# FatPapa1_ISTA.net
KiCad netlist of a schematic drawn in EAGLE
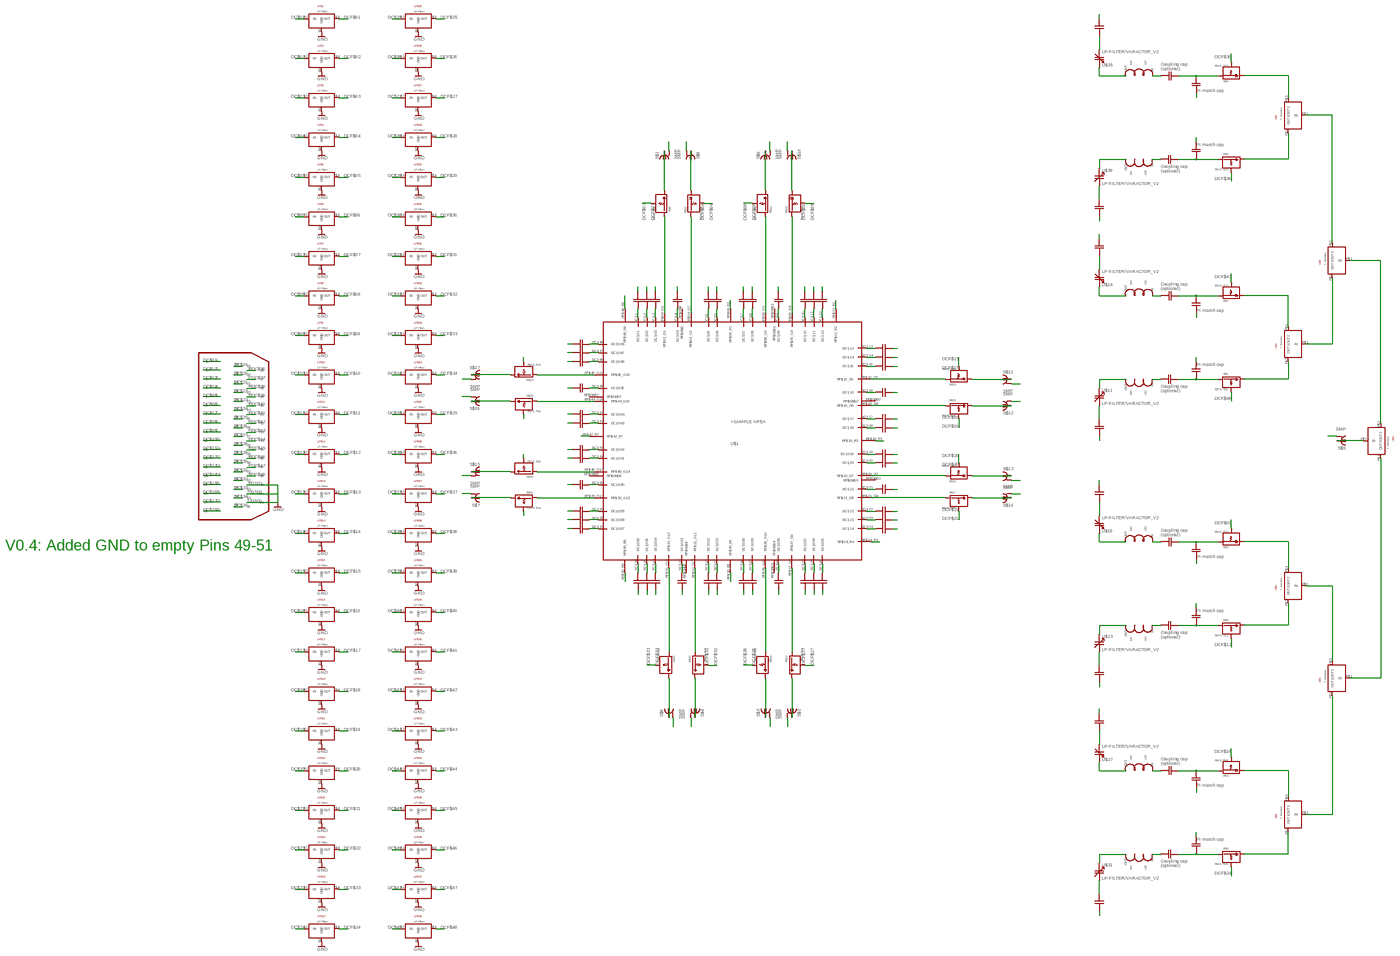
[diagram p0: schematic, sheet 1, overview]
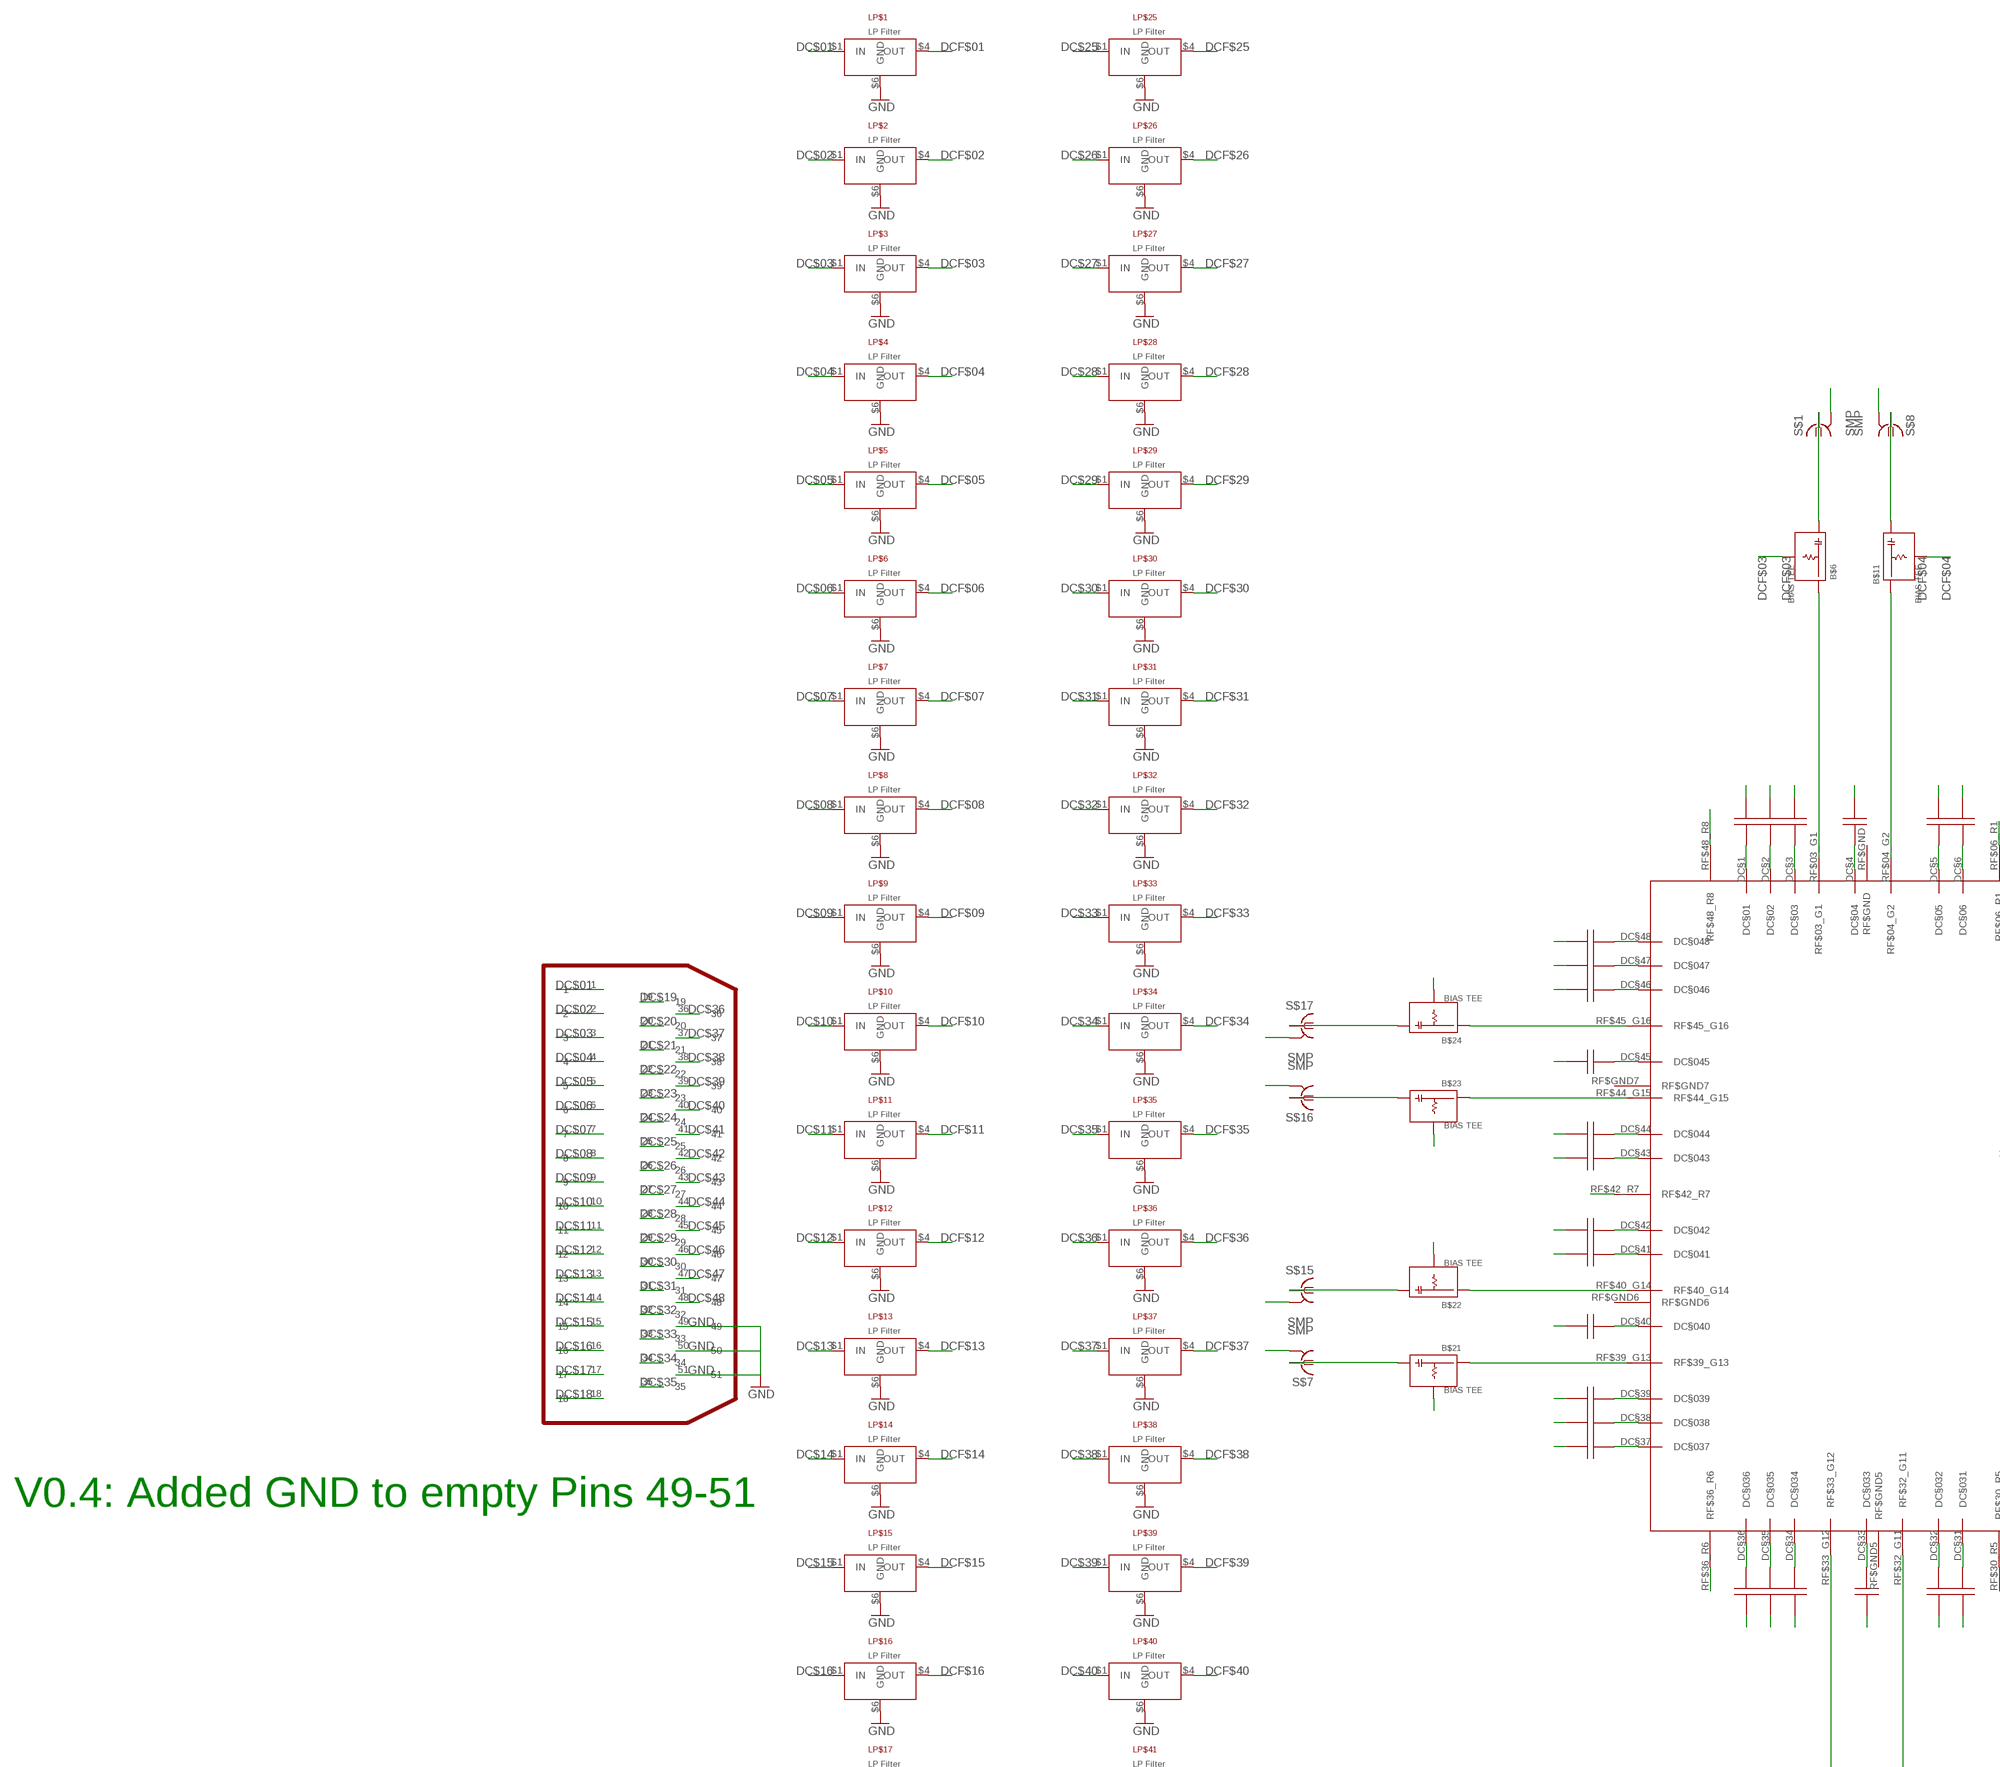
[diagram p1: schematic, sheet 1, part 1 of 4]
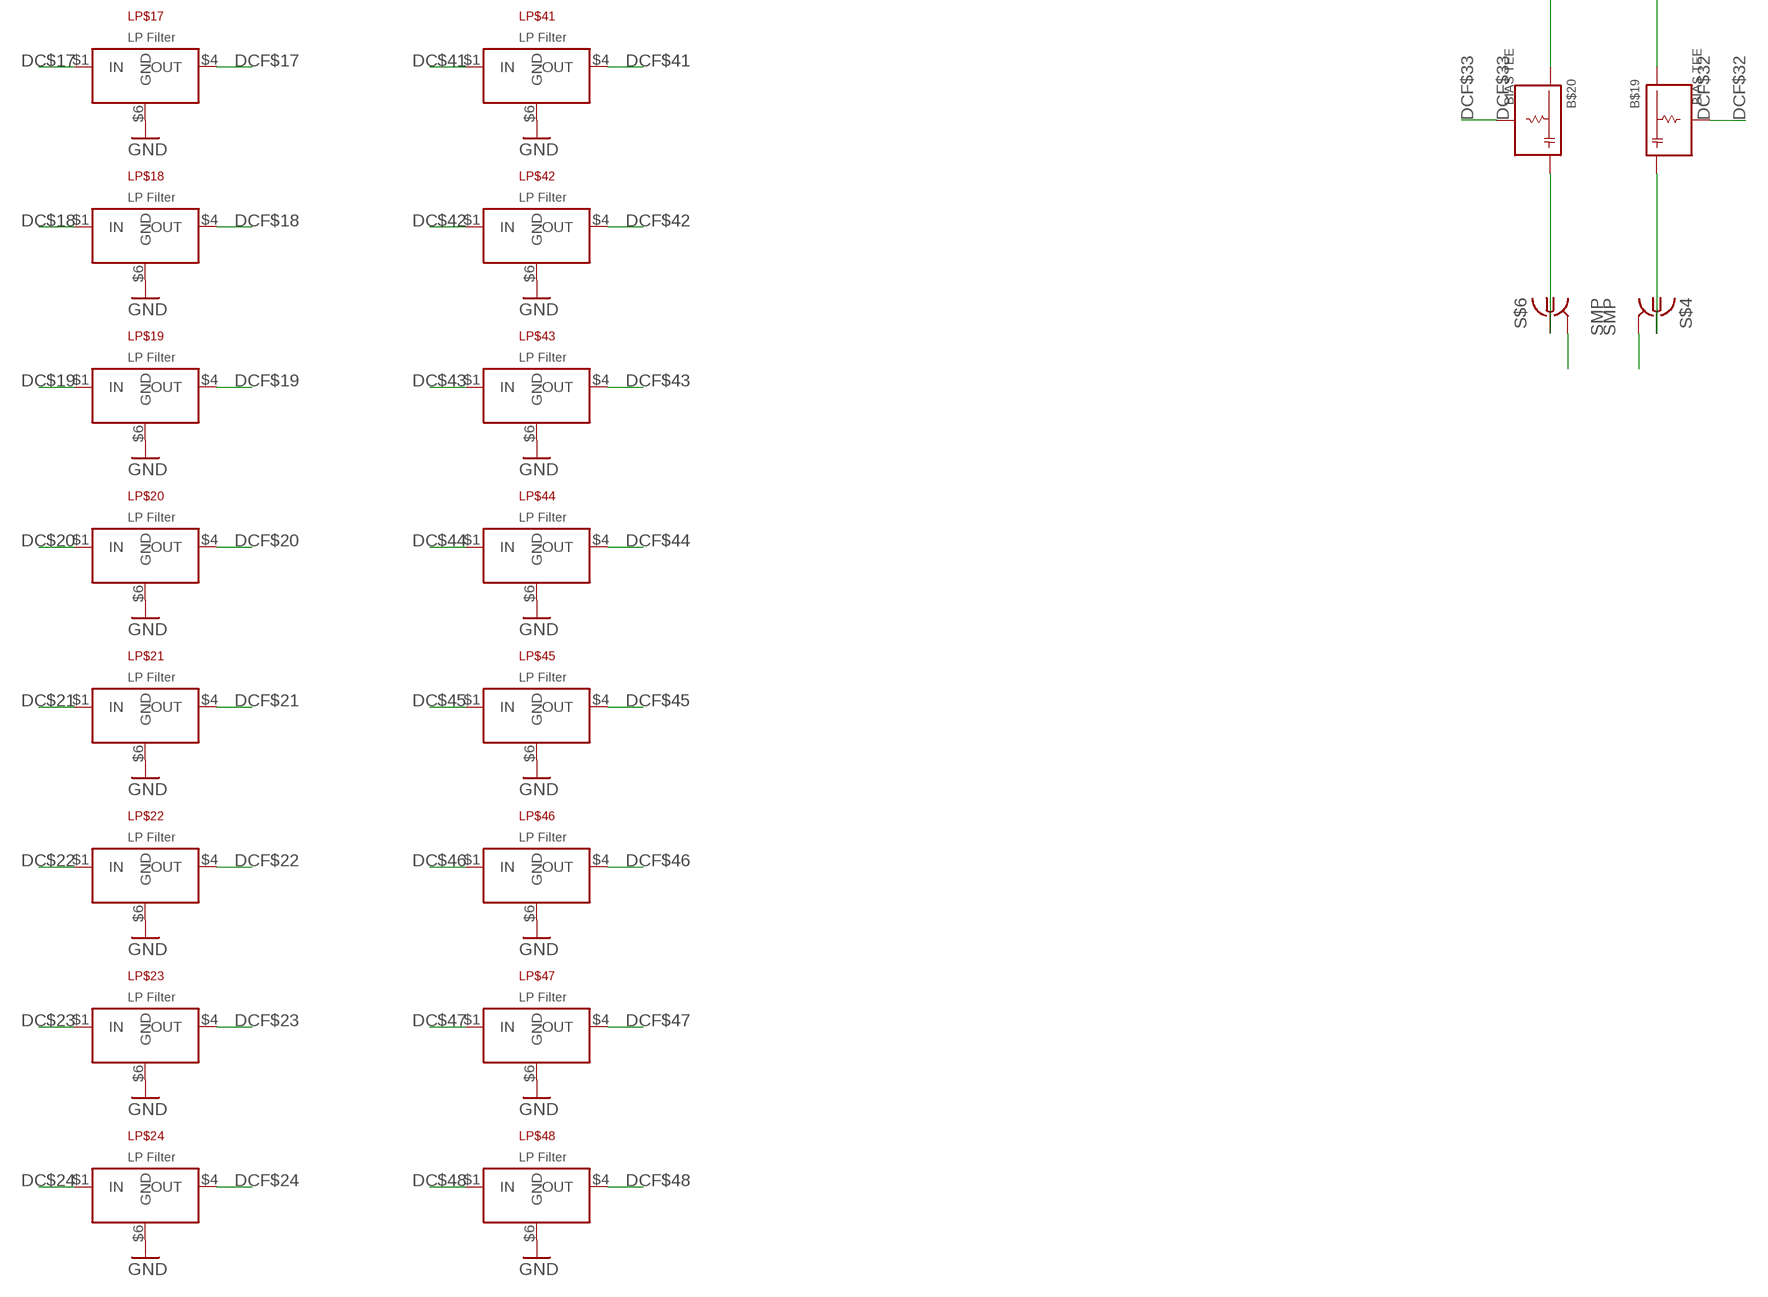
[diagram p2: schematic, sheet 1, part 2 of 4]
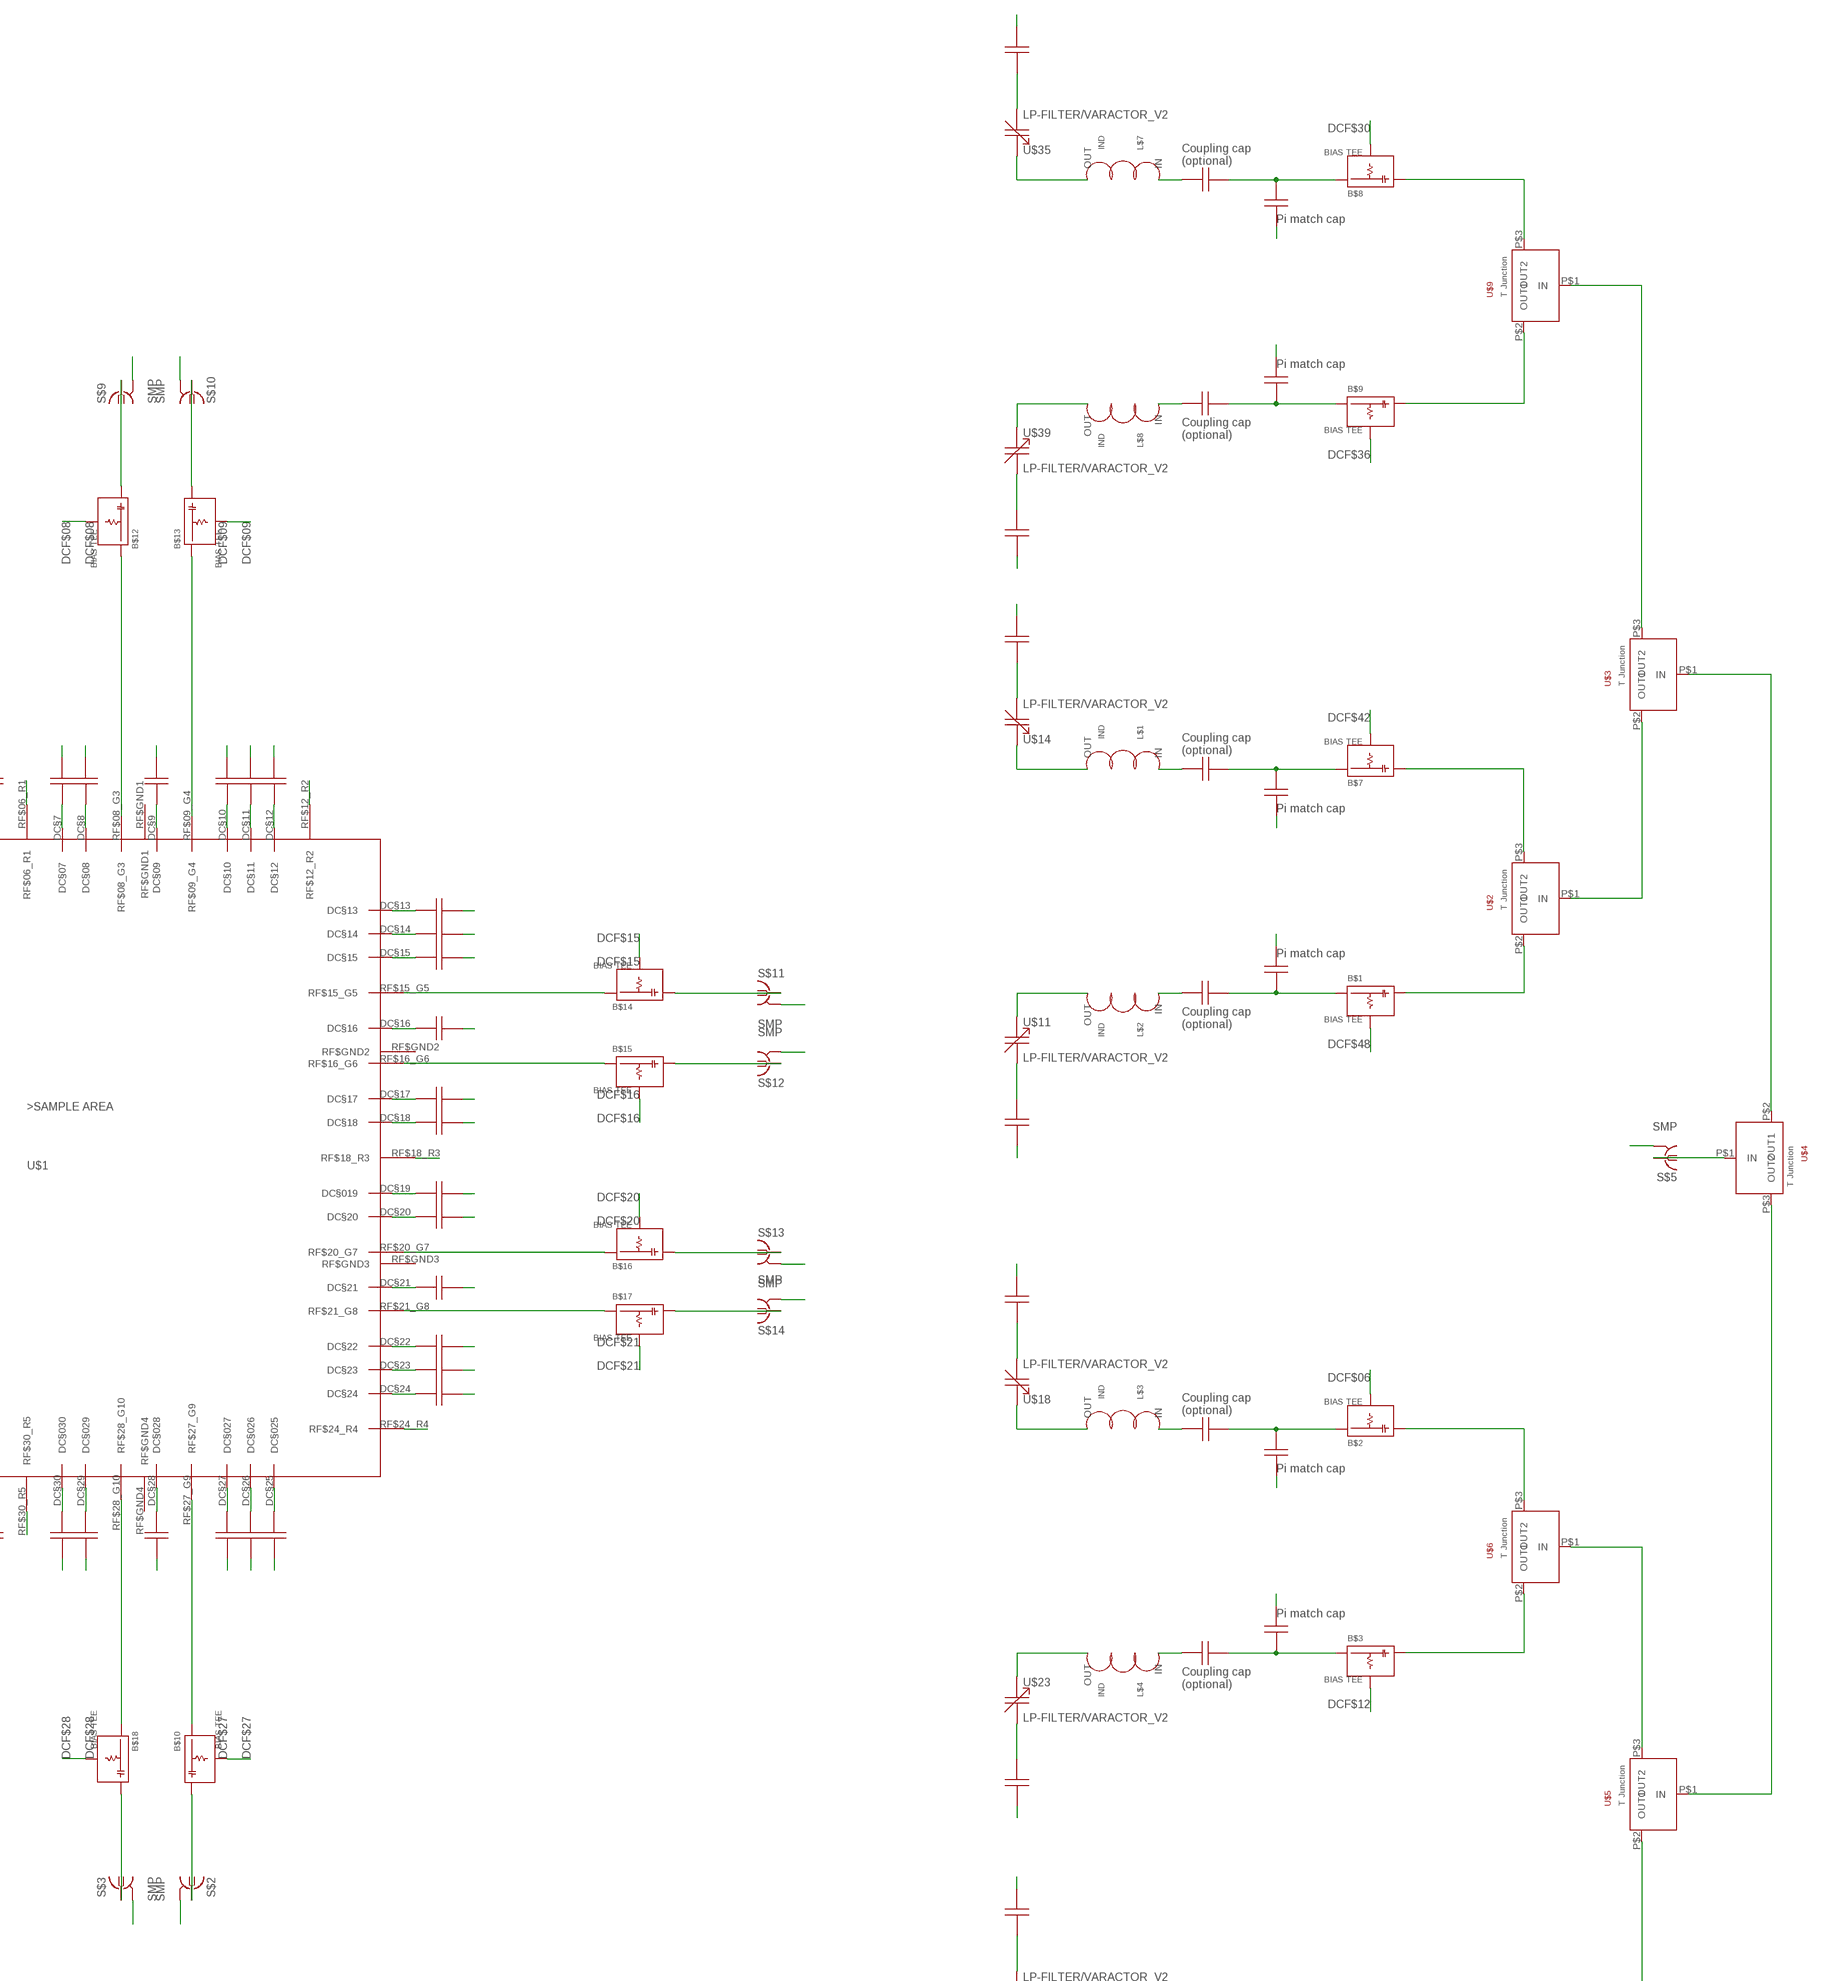
[diagram p3: schematic, sheet 1, part 3 of 4]
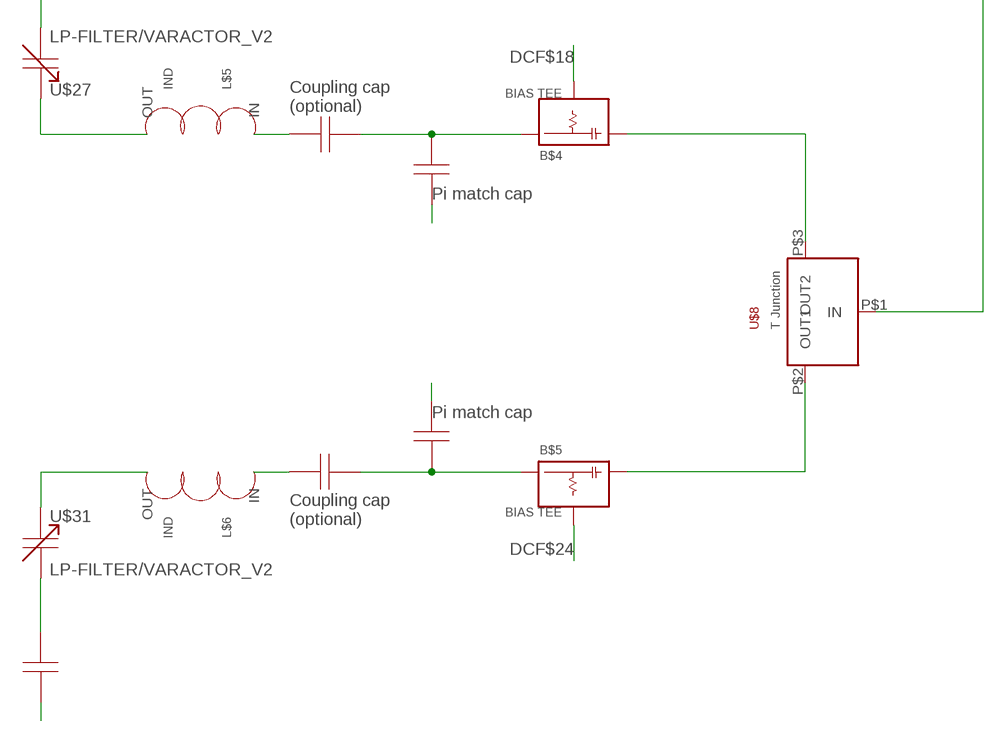
[diagram p4: schematic, sheet 1, part 4 of 4]

(export (version "E")
  (design (tool "Eeschema 10.0.6"))
  (components
    (comp (ref "B$1")
      (value "BIASTEEUP1")
      (footprint "eagle-import:BIAS_TEE_UP_0603")
      (libsource (lib "eagle-import") (part "BIASTEEUP1"))
    )
    (comp (ref "B$2")
      (value "BIASTEEUP1")
      (footprint "eagle-import:BIAS_TEE_UP_0603")
      (libsource (lib "eagle-import") (part "BIASTEEUP1"))
    )
    (comp (ref "B$3")
      (value "BIASTEEUP1")
      (footprint "eagle-import:BIAS_TEE_UP_0603")
      (libsource (lib "eagle-import") (part "BIASTEEUP1"))
    )
    (comp (ref "B$4")
      (value "BIASTEEUP1")
      (footprint "eagle-import:BIAS_TEE_UP_0603")
      (libsource (lib "eagle-import") (part "BIASTEEUP1"))
    )
    (comp (ref "B$5")
      (value "BIASTEEUP1")
      (footprint "eagle-import:BIAS_TEE_UP_0603")
      (libsource (lib "eagle-import") (part "BIASTEEUP1"))
    )
    (comp (ref "B$6")
      (value "BIASTEEDOWN1")
      (footprint "eagle-import:BIAS_TEE_DOWN_0603")
      (libsource (lib "eagle-import") (part "BIASTEEDOWN1"))
    )
    (comp (ref "B$7")
      (value "BIASTEEUP1")
      (footprint "eagle-import:BIAS_TEE_UP_0603")
      (libsource (lib "eagle-import") (part "BIASTEEUP1"))
    )
    (comp (ref "B$8")
      (value "BIASTEEUP1")
      (footprint "eagle-import:BIAS_TEE_UP_0603")
      (libsource (lib "eagle-import") (part "BIASTEEUP1"))
    )
    (comp (ref "B$9")
      (value "BIASTEEUP1")
      (footprint "eagle-import:BIAS_TEE_UP_0603")
      (libsource (lib "eagle-import") (part "BIASTEEUP1"))
    )
    (comp (ref "B$10")
      (value "BIASTEEDOWN1")
      (footprint "eagle-import:BIAS_TEE_DOWN_0603")
      (libsource (lib "eagle-import") (part "BIASTEEDOWN1"))
    )
    (comp (ref "B$11")
      (value "BIASTEEDOWN1")
      (footprint "eagle-import:BIAS_TEE_DOWN_0603")
      (libsource (lib "eagle-import") (part "BIASTEEDOWN1"))
    )
    (comp (ref "B$12")
      (value "BIASTEEUP1")
      (footprint "eagle-import:BIAS_TEE_UP_0603")
      (libsource (lib "eagle-import") (part "BIASTEEUP1"))
    )
    (comp (ref "B$13")
      (value "BIASTEEUP1")
      (footprint "eagle-import:BIAS_TEE_UP_0603")
      (libsource (lib "eagle-import") (part "BIASTEEUP1"))
    )
    (comp (ref "B$14")
      (value "BIASTEEDOWN1")
      (footprint "eagle-import:BIAS_TEE_DOWN_0603")
      (libsource (lib "eagle-import") (part "BIASTEEDOWN1"))
    )
    (comp (ref "B$15")
      (value "BIASTEEDOWN1")
      (footprint "eagle-import:BIAS_TEE_DOWN_0603")
      (libsource (lib "eagle-import") (part "BIASTEEDOWN1"))
    )
    (comp (ref "B$16")
      (value "BIASTEEUP1")
      (footprint "eagle-import:BIAS_TEE_UP_0603")
      (libsource (lib "eagle-import") (part "BIASTEEUP1"))
    )
    (comp (ref "B$17")
      (value "BIASTEEUP1")
      (footprint "eagle-import:BIAS_TEE_UP_0603")
      (libsource (lib "eagle-import") (part "BIASTEEUP1"))
    )
    (comp (ref "B$18")
      (value "BIASTEEDOWN1")
      (footprint "eagle-import:BIAS_TEE_DOWN_0603")
      (libsource (lib "eagle-import") (part "BIASTEEDOWN1"))
    )
    (comp (ref "B$19")
      (value "BIASTEEUP1")
      (footprint "eagle-import:BIAS_TEE_UP_0603")
      (libsource (lib "eagle-import") (part "BIASTEEUP1"))
    )
    (comp (ref "B$20")
      (value "BIASTEEUP1")
      (footprint "eagle-import:BIAS_TEE_UP_0603")
      (libsource (lib "eagle-import") (part "BIASTEEUP1"))
    )
    (comp (ref "B$21")
      (value "BIASTEEDOWN1")
      (footprint "eagle-import:BIAS_TEE_DOWN_0603")
      (libsource (lib "eagle-import") (part "BIASTEEDOWN1"))
    )
    (comp (ref "B$22")
      (value "BIASTEEDOWN1")
      (footprint "eagle-import:BIAS_TEE_DOWN_0603")
      (libsource (lib "eagle-import") (part "BIASTEEDOWN1"))
    )
    (comp (ref "B$23")
      (value "BIASTEEUP1")
      (footprint "eagle-import:BIAS_TEE_UP_0603")
      (libsource (lib "eagle-import") (part "BIASTEEUP1"))
    )
    (comp (ref "B$24")
      (value "BIASTEEUP1")
      (footprint "eagle-import:BIAS_TEE_UP_0603")
      (libsource (lib "eagle-import") (part "BIASTEEUP1"))
    )
    (comp (ref "L$1")
      (value "L_MATCH")
      (footprint "eagle-import:L_MATCH")
      (libsource (lib "eagle-import") (part "L_MATCH"))
    )
    (comp (ref "L$2")
      (value "L_MATCH")
      (footprint "eagle-import:L_MATCH")
      (libsource (lib "eagle-import") (part "L_MATCH"))
    )
    (comp (ref "L$3")
      (value "L_MATCH")
      (footprint "eagle-import:L_MATCH")
      (libsource (lib "eagle-import") (part "L_MATCH"))
    )
    (comp (ref "L$4")
      (value "L_MATCH")
      (footprint "eagle-import:L_MATCH")
      (libsource (lib "eagle-import") (part "L_MATCH"))
    )
    (comp (ref "L$5")
      (value "L_MATCH")
      (footprint "eagle-import:L_MATCH")
      (libsource (lib "eagle-import") (part "L_MATCH"))
    )
    (comp (ref "L$6")
      (value "L_MATCH")
      (footprint "eagle-import:L_MATCH")
      (libsource (lib "eagle-import") (part "L_MATCH"))
    )
    (comp (ref "L$7")
      (value "L_MATCH")
      (footprint "eagle-import:L_MATCH")
      (libsource (lib "eagle-import") (part "L_MATCH"))
    )
    (comp (ref "L$8")
      (value "L_MATCH")
      (footprint "eagle-import:L_MATCH")
      (libsource (lib "eagle-import") (part "L_MATCH"))
    )
    (comp (ref "LP$1")
      (value "LP-FILTER/1-STAGETOP")
      (footprint "eagle-import:LP-FILTER_1_STAGE_OS_0603_TOP")
      (libsource (lib "eagle-import") (part "LP-FILTER/1-STAGETOP"))
    )
    (comp (ref "LP$2")
      (value "LP-FILTER/1-STAGETOP")
      (footprint "eagle-import:LP-FILTER_1_STAGE_OS_0603_TOP")
      (libsource (lib "eagle-import") (part "LP-FILTER/1-STAGETOP"))
    )
    (comp (ref "LP$3")
      (value "LP-FILTER/1-STAGETOP")
      (footprint "eagle-import:LP-FILTER_1_STAGE_OS_0603_TOP")
      (libsource (lib "eagle-import") (part "LP-FILTER/1-STAGETOP"))
    )
    (comp (ref "LP$4")
      (value "LP-FILTER/1-STAGETOP")
      (footprint "eagle-import:LP-FILTER_1_STAGE_OS_0603_TOP")
      (libsource (lib "eagle-import") (part "LP-FILTER/1-STAGETOP"))
    )
    (comp (ref "LP$5")
      (value "LP-FILTER/1-STAGETOP")
      (footprint "eagle-import:LP-FILTER_1_STAGE_OS_0603_TOP")
      (libsource (lib "eagle-import") (part "LP-FILTER/1-STAGETOP"))
    )
    (comp (ref "LP$6")
      (value "LP-FILTER/1-STAGETOP")
      (footprint "eagle-import:LP-FILTER_1_STAGE_OS_0603_TOP")
      (libsource (lib "eagle-import") (part "LP-FILTER/1-STAGETOP"))
    )
    (comp (ref "LP$7")
      (value "LP-FILTER/1-STAGETOP")
      (footprint "eagle-import:LP-FILTER_1_STAGE_OS_0603_TOP")
      (libsource (lib "eagle-import") (part "LP-FILTER/1-STAGETOP"))
    )
    (comp (ref "LP$8")
      (value "LP-FILTER/1-STAGETOP")
      (footprint "eagle-import:LP-FILTER_1_STAGE_OS_0603_TOP")
      (libsource (lib "eagle-import") (part "LP-FILTER/1-STAGETOP"))
    )
    (comp (ref "LP$9")
      (value "LP-FILTER/1-STAGETOP")
      (footprint "eagle-import:LP-FILTER_1_STAGE_OS_0603_TOP")
      (libsource (lib "eagle-import") (part "LP-FILTER/1-STAGETOP"))
    )
    (comp (ref "LP$10")
      (value "LP-FILTER/1-STAGETOP")
      (footprint "eagle-import:LP-FILTER_1_STAGE_OS_0603_TOP")
      (libsource (lib "eagle-import") (part "LP-FILTER/1-STAGETOP"))
    )
    (comp (ref "LP$11")
      (value "LP-FILTER/1-STAGETOP")
      (footprint "eagle-import:LP-FILTER_1_STAGE_OS_0603_TOP")
      (libsource (lib "eagle-import") (part "LP-FILTER/1-STAGETOP"))
    )
    (comp (ref "LP$12")
      (value "LP-FILTER/1-STAGETOP")
      (footprint "eagle-import:LP-FILTER_1_STAGE_OS_0603_TOP")
      (libsource (lib "eagle-import") (part "LP-FILTER/1-STAGETOP"))
    )
    (comp (ref "LP$13")
      (value "LP-FILTER/1-STAGETOP")
      (footprint "eagle-import:LP-FILTER_1_STAGE_OS_0603_TOP")
      (libsource (lib "eagle-import") (part "LP-FILTER/1-STAGETOP"))
    )
    (comp (ref "LP$14")
      (value "LP-FILTER/1-STAGETOP")
      (footprint "eagle-import:LP-FILTER_1_STAGE_OS_0603_TOP")
      (libsource (lib "eagle-import") (part "LP-FILTER/1-STAGETOP"))
    )
    (comp (ref "LP$15")
      (value "LP-FILTER/1-STAGETOP")
      (footprint "eagle-import:LP-FILTER_1_STAGE_OS_0603_TOP")
      (libsource (lib "eagle-import") (part "LP-FILTER/1-STAGETOP"))
    )
    (comp (ref "LP$16")
      (value "LP-FILTER/1-STAGETOP")
      (footprint "eagle-import:LP-FILTER_1_STAGE_OS_0603_TOP")
      (libsource (lib "eagle-import") (part "LP-FILTER/1-STAGETOP"))
    )
    (comp (ref "LP$17")
      (value "LP-FILTER/1-STAGETOP")
      (footprint "eagle-import:LP-FILTER_1_STAGE_OS_0603_TOP")
      (libsource (lib "eagle-import") (part "LP-FILTER/1-STAGETOP"))
    )
    (comp (ref "LP$18")
      (value "LP-FILTER/1-STAGETOP")
      (footprint "eagle-import:LP-FILTER_1_STAGE_OS_0603_TOP")
      (libsource (lib "eagle-import") (part "LP-FILTER/1-STAGETOP"))
    )
    (comp (ref "LP$19")
      (value "LP-FILTER/1-STAGETOP")
      (footprint "eagle-import:LP-FILTER_1_STAGE_OS_0603_TOP")
      (libsource (lib "eagle-import") (part "LP-FILTER/1-STAGETOP"))
    )
    (comp (ref "LP$20")
      (value "LP-FILTER/1-STAGETOP")
      (footprint "eagle-import:LP-FILTER_1_STAGE_OS_0603_TOP")
      (libsource (lib "eagle-import") (part "LP-FILTER/1-STAGETOP"))
    )
    (comp (ref "LP$21")
      (value "LP-FILTER/1-STAGETOP")
      (footprint "eagle-import:LP-FILTER_1_STAGE_OS_0603_TOP")
      (libsource (lib "eagle-import") (part "LP-FILTER/1-STAGETOP"))
    )
    (comp (ref "LP$22")
      (value "LP-FILTER/1-STAGETOP")
      (footprint "eagle-import:LP-FILTER_1_STAGE_OS_0603_TOP")
      (libsource (lib "eagle-import") (part "LP-FILTER/1-STAGETOP"))
    )
    (comp (ref "LP$23")
      (value "LP-FILTER/1-STAGETOP")
      (footprint "eagle-import:LP-FILTER_1_STAGE_OS_0603_TOP")
      (libsource (lib "eagle-import") (part "LP-FILTER/1-STAGETOP"))
    )
    (comp (ref "LP$24")
      (value "LP-FILTER/1-STAGETOP")
      (footprint "eagle-import:LP-FILTER_1_STAGE_OS_0603_TOP")
      (libsource (lib "eagle-import") (part "LP-FILTER/1-STAGETOP"))
    )
    (comp (ref "LP$25")
      (value "LP-FILTER/1-STAGETOP")
      (footprint "eagle-import:LP-FILTER_1_STAGE_OS_0603_TOP")
      (libsource (lib "eagle-import") (part "LP-FILTER/1-STAGETOP"))
    )
    (comp (ref "LP$26")
      (value "LP-FILTER/1-STAGETOP")
      (footprint "eagle-import:LP-FILTER_1_STAGE_OS_0603_TOP")
      (libsource (lib "eagle-import") (part "LP-FILTER/1-STAGETOP"))
    )
    (comp (ref "LP$27")
      (value "LP-FILTER/1-STAGETOP")
      (footprint "eagle-import:LP-FILTER_1_STAGE_OS_0603_TOP")
      (libsource (lib "eagle-import") (part "LP-FILTER/1-STAGETOP"))
    )
    (comp (ref "LP$28")
      (value "LP-FILTER/1-STAGETOP")
      (footprint "eagle-import:LP-FILTER_1_STAGE_OS_0603_TOP")
      (libsource (lib "eagle-import") (part "LP-FILTER/1-STAGETOP"))
    )
    (comp (ref "LP$29")
      (value "LP-FILTER/1-STAGETOP")
      (footprint "eagle-import:LP-FILTER_1_STAGE_OS_0603_TOP")
      (libsource (lib "eagle-import") (part "LP-FILTER/1-STAGETOP"))
    )
    (comp (ref "LP$30")
      (value "LP-FILTER/1-STAGETOP")
      (footprint "eagle-import:LP-FILTER_1_STAGE_OS_0603_TOP")
      (libsource (lib "eagle-import") (part "LP-FILTER/1-STAGETOP"))
    )
    (comp (ref "LP$31")
      (value "LP-FILTER/1-STAGETOP")
      (footprint "eagle-import:LP-FILTER_1_STAGE_OS_0603_TOP")
      (libsource (lib "eagle-import") (part "LP-FILTER/1-STAGETOP"))
    )
    (comp (ref "LP$32")
      (value "LP-FILTER/1-STAGETOP")
      (footprint "eagle-import:LP-FILTER_1_STAGE_OS_0603_TOP")
      (libsource (lib "eagle-import") (part "LP-FILTER/1-STAGETOP"))
    )
    (comp (ref "LP$33")
      (value "LP-FILTER/1-STAGETOP")
      (footprint "eagle-import:LP-FILTER_1_STAGE_OS_0603_TOP")
      (libsource (lib "eagle-import") (part "LP-FILTER/1-STAGETOP"))
    )
    (comp (ref "LP$34")
      (value "LP-FILTER/1-STAGETOP")
      (footprint "eagle-import:LP-FILTER_1_STAGE_OS_0603_TOP")
      (libsource (lib "eagle-import") (part "LP-FILTER/1-STAGETOP"))
    )
    (comp (ref "LP$35")
      (value "LP-FILTER/1-STAGETOP")
      (footprint "eagle-import:LP-FILTER_1_STAGE_OS_0603_TOP")
      (libsource (lib "eagle-import") (part "LP-FILTER/1-STAGETOP"))
    )
    (comp (ref "LP$36")
      (value "LP-FILTER/1-STAGETOP")
      (footprint "eagle-import:LP-FILTER_1_STAGE_OS_0603_TOP")
      (libsource (lib "eagle-import") (part "LP-FILTER/1-STAGETOP"))
    )
    (comp (ref "LP$37")
      (value "LP-FILTER/1-STAGETOP")
      (footprint "eagle-import:LP-FILTER_1_STAGE_OS_0603_TOP")
      (libsource (lib "eagle-import") (part "LP-FILTER/1-STAGETOP"))
    )
    (comp (ref "LP$38")
      (value "LP-FILTER/1-STAGETOP")
      (footprint "eagle-import:LP-FILTER_1_STAGE_OS_0603_TOP")
      (libsource (lib "eagle-import") (part "LP-FILTER/1-STAGETOP"))
    )
    (comp (ref "LP$39")
      (value "LP-FILTER/1-STAGETOP")
      (footprint "eagle-import:LP-FILTER_1_STAGE_OS_0603_TOP")
      (libsource (lib "eagle-import") (part "LP-FILTER/1-STAGETOP"))
    )
    (comp (ref "LP$40")
      (value "LP-FILTER/1-STAGETOP")
      (footprint "eagle-import:LP-FILTER_1_STAGE_OS_0603_TOP")
      (libsource (lib "eagle-import") (part "LP-FILTER/1-STAGETOP"))
    )
    (comp (ref "LP$41")
      (value "LP-FILTER/1-STAGETOP")
      (footprint "eagle-import:LP-FILTER_1_STAGE_OS_0603_TOP")
      (libsource (lib "eagle-import") (part "LP-FILTER/1-STAGETOP"))
    )
    (comp (ref "LP$42")
      (value "LP-FILTER/1-STAGETOP")
      (footprint "eagle-import:LP-FILTER_1_STAGE_OS_0603_TOP")
      (libsource (lib "eagle-import") (part "LP-FILTER/1-STAGETOP"))
    )
    (comp (ref "LP$43")
      (value "LP-FILTER/1-STAGETOP")
      (footprint "eagle-import:LP-FILTER_1_STAGE_OS_0603_TOP")
      (libsource (lib "eagle-import") (part "LP-FILTER/1-STAGETOP"))
    )
    (comp (ref "LP$44")
      (value "LP-FILTER/1-STAGETOP")
      (footprint "eagle-import:LP-FILTER_1_STAGE_OS_0603_TOP")
      (libsource (lib "eagle-import") (part "LP-FILTER/1-STAGETOP"))
    )
    (comp (ref "LP$45")
      (value "LP-FILTER/1-STAGETOP")
      (footprint "eagle-import:LP-FILTER_1_STAGE_OS_0603_TOP")
      (libsource (lib "eagle-import") (part "LP-FILTER/1-STAGETOP"))
    )
    (comp (ref "LP$46")
      (value "LP-FILTER/1-STAGETOP")
      (footprint "eagle-import:LP-FILTER_1_STAGE_OS_0603_TOP")
      (libsource (lib "eagle-import") (part "LP-FILTER/1-STAGETOP"))
    )
    (comp (ref "LP$47")
      (value "LP-FILTER/1-STAGETOP")
      (footprint "eagle-import:LP-FILTER_1_STAGE_OS_0603_TOP")
      (libsource (lib "eagle-import") (part "LP-FILTER/1-STAGETOP"))
    )
    (comp (ref "LP$48")
      (value "LP-FILTER/1-STAGETOP")
      (footprint "eagle-import:LP-FILTER_1_STAGE_OS_0603_TOP")
      (libsource (lib "eagle-import") (part "LP-FILTER/1-STAGETOP"))
    )
    (comp (ref "S$1")
      (value "MC-921WIDE")
      (footprint "eagle-import:SMP_STRAIGHT_MINI_WIDE")
      (libsource (lib "eagle-import") (part "MC-921WIDE"))
    )
    (comp (ref "S$2")
      (value "MC-921WIDE")
      (footprint "eagle-import:SMP_STRAIGHT_MINI_WIDE")
      (libsource (lib "eagle-import") (part "MC-921WIDE"))
    )
    (comp (ref "S$3")
      (value "MC-921WIDE")
      (footprint "eagle-import:SMP_STRAIGHT_MINI_WIDE")
      (libsource (lib "eagle-import") (part "MC-921WIDE"))
    )
    (comp (ref "S$4")
      (value "MC-921WIDE")
      (footprint "eagle-import:SMP_STRAIGHT_MINI_WIDE")
      (libsource (lib "eagle-import") (part "MC-921WIDE"))
    )
    (comp (ref "S$5")
      (value "MC-921WIDE")
      (footprint "eagle-import:SMP_STRAIGHT_MINI_WIDE")
      (libsource (lib "eagle-import") (part "MC-921WIDE"))
    )
    (comp (ref "S$6")
      (value "MC-921WIDE")
      (footprint "eagle-import:SMP_STRAIGHT_MINI_WIDE")
      (libsource (lib "eagle-import") (part "MC-921WIDE"))
    )
    (comp (ref "S$7")
      (value "MC-921WIDE")
      (footprint "eagle-import:SMP_STRAIGHT_MINI_WIDE")
      (libsource (lib "eagle-import") (part "MC-921WIDE"))
    )
    (comp (ref "S$8")
      (value "MC-921WIDE")
      (footprint "eagle-import:SMP_STRAIGHT_MINI_WIDE")
      (libsource (lib "eagle-import") (part "MC-921WIDE"))
    )
    (comp (ref "S$9")
      (value "MC-921WIDE")
      (footprint "eagle-import:SMP_STRAIGHT_MINI_WIDE")
      (libsource (lib "eagle-import") (part "MC-921WIDE"))
    )
    (comp (ref "S$10")
      (value "MC-921WIDE")
      (footprint "eagle-import:SMP_STRAIGHT_MINI_WIDE")
      (libsource (lib "eagle-import") (part "MC-921WIDE"))
    )
    (comp (ref "S$11")
      (value "MC-921WIDE")
      (footprint "eagle-import:SMP_STRAIGHT_MINI_WIDE")
      (libsource (lib "eagle-import") (part "MC-921WIDE"))
    )
    (comp (ref "S$12")
      (value "MC-921WIDE")
      (footprint "eagle-import:SMP_STRAIGHT_MINI_WIDE")
      (libsource (lib "eagle-import") (part "MC-921WIDE"))
    )
    (comp (ref "S$13")
      (value "MC-921WIDE")
      (footprint "eagle-import:SMP_STRAIGHT_MINI_WIDE")
      (libsource (lib "eagle-import") (part "MC-921WIDE"))
    )
    (comp (ref "S$14")
      (value "MC-921WIDE")
      (footprint "eagle-import:SMP_STRAIGHT_MINI_WIDE")
      (libsource (lib "eagle-import") (part "MC-921WIDE"))
    )
    (comp (ref "S$15")
      (value "MC-921WIDE")
      (footprint "eagle-import:SMP_STRAIGHT_MINI_WIDE")
      (libsource (lib "eagle-import") (part "MC-921WIDE"))
    )
    (comp (ref "S$16")
      (value "MC-921WIDE")
      (footprint "eagle-import:SMP_STRAIGHT_MINI_WIDE")
      (libsource (lib "eagle-import") (part "MC-921WIDE"))
    )
    (comp (ref "S$17")
      (value "MC-921WIDE")
      (footprint "eagle-import:SMP_STRAIGHT_MINI_WIDE")
      (libsource (lib "eagle-import") (part "MC-921WIDE"))
    )
    (comp (ref "U$1")
      (value "48DC+24RF_V3.0")
      (footprint "eagle-import:48DC+24RF_V3.0")
      (libsource (lib "eagle-import") (part "48DC+24RF_V3.0"))
    )
    (comp (ref "U$2")
      (value "TJUNCTION")
      (footprint "eagle-import:T_JUNCTION_0.3MM")
      (libsource (lib "eagle-import") (part "TJUNCTION"))
    )
    (comp (ref "U$3")
      (value "TJUNCTION")
      (footprint "eagle-import:T_JUNCTION_0.3MM")
      (libsource (lib "eagle-import") (part "TJUNCTION"))
    )
    (comp (ref "U$4")
      (value "TJUNCTION")
      (footprint "eagle-import:T_JUNCTION_0.3MM")
      (libsource (lib "eagle-import") (part "TJUNCTION"))
    )
    (comp (ref "U$5")
      (value "TJUNCTION")
      (footprint "eagle-import:T_JUNCTION_0.3MM")
      (libsource (lib "eagle-import") (part "TJUNCTION"))
    )
    (comp (ref "U$6")
      (value "TJUNCTION")
      (footprint "eagle-import:T_JUNCTION_0.3MM")
      (libsource (lib "eagle-import") (part "TJUNCTION"))
    )
    (comp (ref "U$7")
      (value "LP-FILTER/CAPACITOR/0603THIN")
      (footprint "eagle-import:LP-FILTER_CAPACITOR_0603_BOTTOM")
      (libsource (lib "eagle-import") (part "LP-FILTER/CAPACITOR/0603THIN"))
    )
    (comp (ref "U$8")
      (value "TJUNCTION")
      (footprint "eagle-import:T_JUNCTION_0.3MM")
      (libsource (lib "eagle-import") (part "TJUNCTION"))
    )
    (comp (ref "U$9")
      (value "TJUNCTION")
      (footprint "eagle-import:T_JUNCTION_0.3MM")
      (libsource (lib "eagle-import") (part "TJUNCTION"))
    )
    (comp (ref "U$10")
      (value "LP-FILTER/CAPACITOR/0603THIN")
      (footprint "eagle-import:LP-FILTER_CAPACITOR_0603_BOTTOM")
      (libsource (lib "eagle-import") (part "LP-FILTER/CAPACITOR/0603THIN"))
    )
    (comp (ref "U$11")
      (value "LP-FILTER/VARACTOR_V2")
      (footprint "eagle-import:LP-FILTER_VARACTOR_V2")
      (libsource (lib "eagle-import") (part "LP-FILTER/VARACTOR_V2"))
    )
    (comp (ref "U$12")
      (value "LP-FILTER/CAPACITOR/0603NORMAL")
      (footprint "eagle-import:LP-FILTER_CAPACITOR_0603_BOTTOM_V2")
      (libsource (lib "eagle-import") (part "LP-FILTER/CAPACITOR/0603NORMAL"))
    )
    (comp (ref "U$13")
      (value "LP-FILTER/CAPACITOR/0603THIN")
      (footprint "eagle-import:LP-FILTER_CAPACITOR_0603_BOTTOM")
      (libsource (lib "eagle-import") (part "LP-FILTER/CAPACITOR/0603THIN"))
    )
    (comp (ref "U$14")
      (value "LP-FILTER/VARACTOR_V2")
      (footprint "eagle-import:LP-FILTER_VARACTOR_V2")
      (libsource (lib "eagle-import") (part "LP-FILTER/VARACTOR_V2"))
    )
    (comp (ref "U$15")
      (value "LP-FILTER/CAPACITOR/0603NORMAL")
      (footprint "eagle-import:LP-FILTER_CAPACITOR_0603_BOTTOM_V2")
      (libsource (lib "eagle-import") (part "LP-FILTER/CAPACITOR/0603NORMAL"))
    )
    (comp (ref "U$16")
      (value "LP-FILTER/CAPACITOR/0603THIN")
      (footprint "eagle-import:LP-FILTER_CAPACITOR_0603_BOTTOM")
      (libsource (lib "eagle-import") (part "LP-FILTER/CAPACITOR/0603THIN"))
    )
    (comp (ref "U$17")
      (value "LP-FILTER/CAPACITOR/0603THIN")
      (footprint "eagle-import:LP-FILTER_CAPACITOR_0603_BOTTOM")
      (libsource (lib "eagle-import") (part "LP-FILTER/CAPACITOR/0603THIN"))
    )
    (comp (ref "U$18")
      (value "LP-FILTER/VARACTOR_V2")
      (footprint "eagle-import:LP-FILTER_VARACTOR_V2")
      (libsource (lib "eagle-import") (part "LP-FILTER/VARACTOR_V2"))
    )
    (comp (ref "U$19")
      (value "LP-FILTER/CAPACITOR/0603NORMAL")
      (footprint "eagle-import:LP-FILTER_CAPACITOR_0603_BOTTOM_V2")
      (libsource (lib "eagle-import") (part "LP-FILTER/CAPACITOR/0603NORMAL"))
    )
    (comp (ref "U$20")
      (value "LP-FILTER/CAPACITOR/0603THIN")
      (footprint "eagle-import:LP-FILTER_CAPACITOR_0603_BOTTOM")
      (libsource (lib "eagle-import") (part "LP-FILTER/CAPACITOR/0603THIN"))
    )
    (comp (ref "U$21")
      (value "LP-FILTER/CAPACITOR/0603THIN")
      (footprint "eagle-import:LP-FILTER_CAPACITOR_0603_BOTTOM")
      (libsource (lib "eagle-import") (part "LP-FILTER/CAPACITOR/0603THIN"))
    )
    (comp (ref "U$22")
      (value "LP-FILTER/CAPACITOR/0603THIN")
      (footprint "eagle-import:LP-FILTER_CAPACITOR_0603_BOTTOM")
      (libsource (lib "eagle-import") (part "LP-FILTER/CAPACITOR/0603THIN"))
    )
    (comp (ref "U$23")
      (value "LP-FILTER/VARACTOR_V2")
      (footprint "eagle-import:LP-FILTER_VARACTOR_V2")
      (libsource (lib "eagle-import") (part "LP-FILTER/VARACTOR_V2"))
    )
    (comp (ref "U$24")
      (value "LP-FILTER/CAPACITOR/0603NORMAL")
      (footprint "eagle-import:LP-FILTER_CAPACITOR_0603_BOTTOM_V2")
      (libsource (lib "eagle-import") (part "LP-FILTER/CAPACITOR/0603NORMAL"))
    )
    (comp (ref "U$25")
      (value "51_PIN_M83513/11-G")
      (footprint "eagle-import:51_PIN_M83513_11-G")
      (libsource (lib "eagle-import") (part "51_PIN_M83513/11-G"))
    )
    (comp (ref "U$26")
      (value "LP-FILTER/CAPACITOR/0603THIN")
      (footprint "eagle-import:LP-FILTER_CAPACITOR_0603_BOTTOM")
      (libsource (lib "eagle-import") (part "LP-FILTER/CAPACITOR/0603THIN"))
    )
    (comp (ref "U$27")
      (value "LP-FILTER/VARACTOR_V2")
      (footprint "eagle-import:LP-FILTER_VARACTOR_V2")
      (libsource (lib "eagle-import") (part "LP-FILTER/VARACTOR_V2"))
    )
    (comp (ref "U$28")
      (value "LP-FILTER/CAPACITOR/0603NORMAL")
      (footprint "eagle-import:LP-FILTER_CAPACITOR_0603_BOTTOM_V2")
      (libsource (lib "eagle-import") (part "LP-FILTER/CAPACITOR/0603NORMAL"))
    )
    (comp (ref "U$29")
      (value "LP-FILTER/CAPACITOR/0603THIN")
      (footprint "eagle-import:LP-FILTER_CAPACITOR_0603_BOTTOM")
      (libsource (lib "eagle-import") (part "LP-FILTER/CAPACITOR/0603THIN"))
    )
    (comp (ref "U$30")
      (value "LP-FILTER/CAPACITOR/0603THIN")
      (footprint "eagle-import:LP-FILTER_CAPACITOR_0603_BOTTOM")
      (libsource (lib "eagle-import") (part "LP-FILTER/CAPACITOR/0603THIN"))
    )
    (comp (ref "U$31")
      (value "LP-FILTER/VARACTOR_V2")
      (footprint "eagle-import:LP-FILTER_VARACTOR_V2")
      (libsource (lib "eagle-import") (part "LP-FILTER/VARACTOR_V2"))
    )
    (comp (ref "U$32")
      (value "LP-FILTER/CAPACITOR/0603NORMAL")
      (footprint "eagle-import:LP-FILTER_CAPACITOR_0603_BOTTOM_V2")
      (libsource (lib "eagle-import") (part "LP-FILTER/CAPACITOR/0603NORMAL"))
    )
    (comp (ref "U$33")
      (value "LP-FILTER/CAPACITOR/0603THIN")
      (footprint "eagle-import:LP-FILTER_CAPACITOR_0603_BOTTOM")
      (libsource (lib "eagle-import") (part "LP-FILTER/CAPACITOR/0603THIN"))
    )
    (comp (ref "U$34")
      (value "LP-FILTER/CAPACITOR/0603THIN")
      (footprint "eagle-import:LP-FILTER_CAPACITOR_0603_BOTTOM")
      (libsource (lib "eagle-import") (part "LP-FILTER/CAPACITOR/0603THIN"))
    )
    (comp (ref "U$35")
      (value "LP-FILTER/VARACTOR_V2")
      (footprint "eagle-import:LP-FILTER_VARACTOR_V2")
      (libsource (lib "eagle-import") (part "LP-FILTER/VARACTOR_V2"))
    )
    (comp (ref "U$36")
      (value "LP-FILTER/CAPACITOR/0603NORMAL")
      (footprint "eagle-import:LP-FILTER_CAPACITOR_0603_BOTTOM_V2")
      (libsource (lib "eagle-import") (part "LP-FILTER/CAPACITOR/0603NORMAL"))
    )
    (comp (ref "U$37")
      (value "LP-FILTER/CAPACITOR/0603THIN")
      (footprint "eagle-import:LP-FILTER_CAPACITOR_0603_BOTTOM")
      (libsource (lib "eagle-import") (part "LP-FILTER/CAPACITOR/0603THIN"))
    )
    (comp (ref "U$38")
      (value "LP-FILTER/CAPACITOR/0603THIN")
      (footprint "eagle-import:LP-FILTER_CAPACITOR_0603_BOTTOM")
      (libsource (lib "eagle-import") (part "LP-FILTER/CAPACITOR/0603THIN"))
    )
    (comp (ref "U$39")
      (value "LP-FILTER/VARACTOR_V2")
      (footprint "eagle-import:LP-FILTER_VARACTOR_V2")
      (libsource (lib "eagle-import") (part "LP-FILTER/VARACTOR_V2"))
    )
    (comp (ref "U$40")
      (value "LP-FILTER/CAPACITOR/0603NORMAL")
      (footprint "eagle-import:LP-FILTER_CAPACITOR_0603_BOTTOM_V2")
      (libsource (lib "eagle-import") (part "LP-FILTER/CAPACITOR/0603NORMAL"))
    )
    (comp (ref "U$41")
      (value "LP-FILTER/CAPACITOR/0603THIN")
      (footprint "eagle-import:LP-FILTER_CAPACITOR_0603_BOTTOM")
      (libsource (lib "eagle-import") (part "LP-FILTER/CAPACITOR/0603THIN"))
    )
    (comp (ref "U$42")
      (value "LP-FILTER/CAPACITOR/0603THIN")
      (footprint "eagle-import:LP-FILTER_CAPACITOR_0603_BOTTOM")
      (libsource (lib "eagle-import") (part "LP-FILTER/CAPACITOR/0603THIN"))
    )
    (comp (ref "U$43")
      (value "LP-FILTER/CAPACITOR/0603THIN")
      (footprint "eagle-import:LP-FILTER_CAPACITOR_0603_BOTTOM")
      (libsource (lib "eagle-import") (part "LP-FILTER/CAPACITOR/0603THIN"))
    )
    (comp (ref "U$44")
      (value "LP-FILTER/CAPACITOR/0603THIN")
      (footprint "eagle-import:LP-FILTER_CAPACITOR_0603_BOTTOM")
      (libsource (lib "eagle-import") (part "LP-FILTER/CAPACITOR/0603THIN"))
    )
    (comp (ref "U$45")
      (value "LP-FILTER/CAPACITOR/0603THIN")
      (footprint "eagle-import:LP-FILTER_CAPACITOR_0603_BOTTOM")
      (libsource (lib "eagle-import") (part "LP-FILTER/CAPACITOR/0603THIN"))
    )
    (comp (ref "U$46")
      (value "LP-FILTER/CAPACITOR/0603THIN")
      (footprint "eagle-import:LP-FILTER_CAPACITOR_0603_BOTTOM")
      (libsource (lib "eagle-import") (part "LP-FILTER/CAPACITOR/0603THIN"))
    )
    (comp (ref "U$47")
      (value "LP-FILTER/CAPACITOR/0603THIN")
      (footprint "eagle-import:LP-FILTER_CAPACITOR_0603_BOTTOM")
      (libsource (lib "eagle-import") (part "LP-FILTER/CAPACITOR/0603THIN"))
    )
    (comp (ref "U$48")
      (value "LP-FILTER/CAPACITOR/0603THIN")
      (footprint "eagle-import:LP-FILTER_CAPACITOR_0603_BOTTOM")
      (libsource (lib "eagle-import") (part "LP-FILTER/CAPACITOR/0603THIN"))
    )
    (comp (ref "U$49")
      (value "LP-FILTER/CAPACITOR/0603THIN")
      (footprint "eagle-import:LP-FILTER_CAPACITOR_0603_BOTTOM")
      (libsource (lib "eagle-import") (part "LP-FILTER/CAPACITOR/0603THIN"))
    )
    (comp (ref "U$50")
      (value "LP-FILTER/CAPACITOR/0603THIN")
      (footprint "eagle-import:LP-FILTER_CAPACITOR_0603_BOTTOM")
      (libsource (lib "eagle-import") (part "LP-FILTER/CAPACITOR/0603THIN"))
    )
    (comp (ref "U$51")
      (value "LP-FILTER/CAPACITOR/0603THIN")
      (footprint "eagle-import:LP-FILTER_CAPACITOR_0603_BOTTOM")
      (libsource (lib "eagle-import") (part "LP-FILTER/CAPACITOR/0603THIN"))
    )
    (comp (ref "U$52")
      (value "LP-FILTER/CAPACITOR/0603THIN")
      (footprint "eagle-import:LP-FILTER_CAPACITOR_0603_BOTTOM")
      (libsource (lib "eagle-import") (part "LP-FILTER/CAPACITOR/0603THIN"))
    )
    (comp (ref "U$53")
      (value "LP-FILTER/CAPACITOR/0603THIN")
      (footprint "eagle-import:LP-FILTER_CAPACITOR_0603_BOTTOM")
      (libsource (lib "eagle-import") (part "LP-FILTER/CAPACITOR/0603THIN"))
    )
    (comp (ref "U$54")
      (value "LP-FILTER/CAPACITOR/0603THIN")
      (footprint "eagle-import:LP-FILTER_CAPACITOR_0603_BOTTOM")
      (libsource (lib "eagle-import") (part "LP-FILTER/CAPACITOR/0603THIN"))
    )
    (comp (ref "U$55")
      (value "LP-FILTER/CAPACITOR/0603THIN")
      (footprint "eagle-import:LP-FILTER_CAPACITOR_0603_BOTTOM")
      (libsource (lib "eagle-import") (part "LP-FILTER/CAPACITOR/0603THIN"))
    )
    (comp (ref "U$56")
      (value "LP-FILTER/CAPACITOR/0603THIN")
      (footprint "eagle-import:LP-FILTER_CAPACITOR_0603_BOTTOM")
      (libsource (lib "eagle-import") (part "LP-FILTER/CAPACITOR/0603THIN"))
    )
    (comp (ref "U$57")
      (value "LP-FILTER/CAPACITOR/0603THIN")
      (footprint "eagle-import:LP-FILTER_CAPACITOR_0603_BOTTOM")
      (libsource (lib "eagle-import") (part "LP-FILTER/CAPACITOR/0603THIN"))
    )
    (comp (ref "U$58")
      (value "LP-FILTER/CAPACITOR/0603THIN")
      (footprint "eagle-import:LP-FILTER_CAPACITOR_0603_BOTTOM")
      (libsource (lib "eagle-import") (part "LP-FILTER/CAPACITOR/0603THIN"))
    )
    (comp (ref "U$59")
      (value "LP-FILTER/CAPACITOR/0603THIN")
      (footprint "eagle-import:LP-FILTER_CAPACITOR_0603_BOTTOM")
      (libsource (lib "eagle-import") (part "LP-FILTER/CAPACITOR/0603THIN"))
    )
    (comp (ref "U$60")
      (value "LP-FILTER/CAPACITOR/0603THIN")
      (footprint "eagle-import:LP-FILTER_CAPACITOR_0603_BOTTOM")
      (libsource (lib "eagle-import") (part "LP-FILTER/CAPACITOR/0603THIN"))
    )
    (comp (ref "U$61")
      (value "LP-FILTER/CAPACITOR/0603THIN")
      (footprint "eagle-import:LP-FILTER_CAPACITOR_0603_BOTTOM")
      (libsource (lib "eagle-import") (part "LP-FILTER/CAPACITOR/0603THIN"))
    )
    (comp (ref "U$62")
      (value "LP-FILTER/CAPACITOR/0603THIN")
      (footprint "eagle-import:LP-FILTER_CAPACITOR_0603_BOTTOM")
      (libsource (lib "eagle-import") (part "LP-FILTER/CAPACITOR/0603THIN"))
    )
    (comp (ref "U$63")
      (value "LP-FILTER/CAPACITOR/0603THIN")
      (footprint "eagle-import:LP-FILTER_CAPACITOR_0603_BOTTOM")
      (libsource (lib "eagle-import") (part "LP-FILTER/CAPACITOR/0603THIN"))
    )
    (comp (ref "U$64")
      (value "LP-FILTER/CAPACITOR/0603THIN")
      (footprint "eagle-import:LP-FILTER_CAPACITOR_0603_BOTTOM")
      (libsource (lib "eagle-import") (part "LP-FILTER/CAPACITOR/0603THIN"))
    )
    (comp (ref "U$65")
      (value "LP-FILTER/CAPACITOR/0603THIN")
      (footprint "eagle-import:LP-FILTER_CAPACITOR_0603_BOTTOM")
      (libsource (lib "eagle-import") (part "LP-FILTER/CAPACITOR/0603THIN"))
    )
    (comp (ref "U$66")
      (value "LP-FILTER/CAPACITOR/0603THIN")
      (footprint "eagle-import:LP-FILTER_CAPACITOR_0603_BOTTOM")
      (libsource (lib "eagle-import") (part "LP-FILTER/CAPACITOR/0603THIN"))
    )
    (comp (ref "U$67")
      (value "LP-FILTER/CAPACITOR/0603THIN")
      (footprint "eagle-import:LP-FILTER_CAPACITOR_0603_BOTTOM")
      (libsource (lib "eagle-import") (part "LP-FILTER/CAPACITOR/0603THIN"))
    )
    (comp (ref "U$68")
      (value "LP-FILTER/CAPACITOR/0603THIN")
      (footprint "eagle-import:LP-FILTER_CAPACITOR_0603_BOTTOM")
      (libsource (lib "eagle-import") (part "LP-FILTER/CAPACITOR/0603THIN"))
    )
    (comp (ref "U$69")
      (value "LP-FILTER/CAPACITOR/0603THIN")
      (footprint "eagle-import:LP-FILTER_CAPACITOR_0603_BOTTOM")
      (libsource (lib "eagle-import") (part "LP-FILTER/CAPACITOR/0603THIN"))
    )
    (comp (ref "U$70")
      (value "LP-FILTER/CAPACITOR/0603THIN")
      (footprint "eagle-import:LP-FILTER_CAPACITOR_0603_BOTTOM")
      (libsource (lib "eagle-import") (part "LP-FILTER/CAPACITOR/0603THIN"))
    )
    (comp (ref "U$71")
      (value "LP-FILTER/CAPACITOR/0603THIN")
      (footprint "eagle-import:LP-FILTER_CAPACITOR_0603_BOTTOM")
      (libsource (lib "eagle-import") (part "LP-FILTER/CAPACITOR/0603THIN"))
    )
    (comp (ref "U$72")
      (value "LP-FILTER/CAPACITOR/0603THIN")
      (footprint "eagle-import:LP-FILTER_CAPACITOR_0603_BOTTOM")
      (libsource (lib "eagle-import") (part "LP-FILTER/CAPACITOR/0603THIN"))
    )
    (comp (ref "U$73")
      (value "LP-FILTER/CAPACITOR/0603THIN")
      (footprint "eagle-import:LP-FILTER_CAPACITOR_0603_BOTTOM")
      (libsource (lib "eagle-import") (part "LP-FILTER/CAPACITOR/0603THIN"))
    )
    (comp (ref "U$74")
      (value "LP-FILTER/CAPACITOR/0603THIN")
      (footprint "eagle-import:LP-FILTER_CAPACITOR_0603_BOTTOM")
      (libsource (lib "eagle-import") (part "LP-FILTER/CAPACITOR/0603THIN"))
    )
    (comp (ref "U$75")
      (value "LP-FILTER/CAPACITOR/0603THIN")
      (footprint "eagle-import:LP-FILTER_CAPACITOR_0603_BOTTOM")
      (libsource (lib "eagle-import") (part "LP-FILTER/CAPACITOR/0603THIN"))
    )
    (comp (ref "U$76")
      (value "LP-FILTER/CAPACITOR/0603THIN")
      (footprint "eagle-import:LP-FILTER_CAPACITOR_0603_BOTTOM")
      (libsource (lib "eagle-import") (part "LP-FILTER/CAPACITOR/0603THIN"))
    )
    (comp (ref "U$77")
      (value "LP-FILTER/CAPACITOR/0603THIN")
      (footprint "eagle-import:LP-FILTER_CAPACITOR_0603_BOTTOM")
      (libsource (lib "eagle-import") (part "LP-FILTER/CAPACITOR/0603THIN"))
    )
    (comp (ref "U$78")
      (value "LP-FILTER/CAPACITOR/0603THIN")
      (footprint "eagle-import:LP-FILTER_CAPACITOR_0603_BOTTOM")
      (libsource (lib "eagle-import") (part "LP-FILTER/CAPACITOR/0603THIN"))
    )
    (comp (ref "U$79")
      (value "LP-FILTER/CAPACITOR/0603THIN")
      (footprint "eagle-import:LP-FILTER_CAPACITOR_0603_BOTTOM")
      (libsource (lib "eagle-import") (part "LP-FILTER/CAPACITOR/0603THIN"))
    )
    (comp (ref "U$80")
      (value "LP-FILTER/CAPACITOR/0603THIN")
      (footprint "eagle-import:LP-FILTER_CAPACITOR_0603_BOTTOM")
      (libsource (lib "eagle-import") (part "LP-FILTER/CAPACITOR/0603THIN"))
    )
    (comp (ref "U$81")
      (value "LP-FILTER/CAPACITOR/0603THIN")
      (footprint "eagle-import:LP-FILTER_CAPACITOR_0603_BOTTOM")
      (libsource (lib "eagle-import") (part "LP-FILTER/CAPACITOR/0603THIN"))
    )
    (comp (ref "U$82")
      (value "LP-FILTER/CAPACITOR/0603THIN")
      (footprint "eagle-import:LP-FILTER_CAPACITOR_0603_BOTTOM")
      (libsource (lib "eagle-import") (part "LP-FILTER/CAPACITOR/0603THIN"))
    )
    (comp (ref "U$83")
      (value "LP-FILTER/CAPACITOR/0603THIN")
      (footprint "eagle-import:LP-FILTER_CAPACITOR_0603_BOTTOM")
      (libsource (lib "eagle-import") (part "LP-FILTER/CAPACITOR/0603THIN"))
    )
    (comp (ref "U$84")
      (value "LP-FILTER/CAPACITOR/0603THIN")
      (footprint "eagle-import:LP-FILTER_CAPACITOR_0603_BOTTOM")
      (libsource (lib "eagle-import") (part "LP-FILTER/CAPACITOR/0603THIN"))
    )
    (comp (ref "U$85")
      (value "LP-FILTER/CAPACITOR/0603THIN")
      (footprint "eagle-import:LP-FILTER_CAPACITOR_0603_BOTTOM")
      (libsource (lib "eagle-import") (part "LP-FILTER/CAPACITOR/0603THIN"))
    )
    (comp (ref "U$86")
      (value "LP-FILTER/CAPACITOR/0603THIN")
      (footprint "eagle-import:LP-FILTER_CAPACITOR_0603_BOTTOM")
      (libsource (lib "eagle-import") (part "LP-FILTER/CAPACITOR/0603THIN"))
    )
    (comp (ref "U$87")
      (value "LP-FILTER/CAPACITOR/0603THIN")
      (footprint "eagle-import:LP-FILTER_CAPACITOR_0603_BOTTOM")
      (libsource (lib "eagle-import") (part "LP-FILTER/CAPACITOR/0603THIN"))
    )
    (comp (ref "U$88")
      (value "LP-FILTER/CAPACITOR/0603THIN")
      (footprint "eagle-import:LP-FILTER_CAPACITOR_0603_BOTTOM")
      (libsource (lib "eagle-import") (part "LP-FILTER/CAPACITOR/0603THIN"))
    )
    (comp (ref "U$89")
      (value "LP-FILTER/CAPACITOR/0603THIN")
      (footprint "eagle-import:LP-FILTER_CAPACITOR_0603_BOTTOM")
      (libsource (lib "eagle-import") (part "LP-FILTER/CAPACITOR/0603THIN"))
    )
  )
  (nets
    (net (code "1") (name "/DC$01") (class "Default")
      (node (ref "LP$1") (pin "$1") (pinfunction "IN_$1") (pintype "bidirectional"))
      (node (ref "U$25") (pin "1") (pinfunction "1_1") (pintype "bidirectional"))
    )
    (net (code "2") (name "/DC$02") (class "Default")
      (node (ref "LP$2") (pin "$1") (pinfunction "IN_$1") (pintype "bidirectional"))
      (node (ref "U$25") (pin "2") (pinfunction "2_2") (pintype "bidirectional"))
    )
    (net (code "3") (name "/DC$03") (class "Default")
      (node (ref "LP$3") (pin "$1") (pinfunction "IN_$1") (pintype "bidirectional"))
      (node (ref "U$25") (pin "3") (pinfunction "3_3") (pintype "bidirectional"))
    )
    (net (code "4") (name "/DC$04") (class "Default")
      (node (ref "LP$4") (pin "$1") (pinfunction "IN_$1") (pintype "bidirectional"))
      (node (ref "U$25") (pin "4") (pinfunction "4_4") (pintype "bidirectional"))
    )
    (net (code "5") (name "/DC$05") (class "Default")
      (node (ref "LP$5") (pin "$1") (pinfunction "IN_$1") (pintype "bidirectional"))
      (node (ref "U$25") (pin "5") (pinfunction "5_5") (pintype "bidirectional"))
    )
    (net (code "6") (name "/DC$06") (class "Default")
      (node (ref "LP$6") (pin "$1") (pinfunction "IN_$1") (pintype "bidirectional"))
      (node (ref "U$25") (pin "6") (pinfunction "6_6") (pintype "bidirectional"))
    )
    (net (code "7") (name "/DC$07") (class "Default")
      (node (ref "LP$7") (pin "$1") (pinfunction "IN_$1") (pintype "bidirectional"))
      (node (ref "U$25") (pin "7") (pinfunction "7_7") (pintype "bidirectional"))
    )
    (net (code "8") (name "/DC$08") (class "Default")
      (node (ref "LP$8") (pin "$1") (pinfunction "IN_$1") (pintype "bidirectional"))
      (node (ref "U$25") (pin "8") (pinfunction "8_8") (pintype "bidirectional"))
    )
    (net (code "9") (name "/DC$09") (class "Default")
      (node (ref "LP$9") (pin "$1") (pinfunction "IN_$1") (pintype "bidirectional"))
      (node (ref "U$25") (pin "9") (pinfunction "9_9") (pintype "bidirectional"))
    )
    (net (code "10") (name "/DC$10") (class "Default")
      (node (ref "LP$10") (pin "$1") (pinfunction "IN_$1") (pintype "bidirectional"))
      (node (ref "U$25") (pin "10") (pinfunction "10_10") (pintype "bidirectional"))
    )
    (net (code "11") (name "/DC$11") (class "Default")
      (node (ref "LP$11") (pin "$1") (pinfunction "IN_$1") (pintype "bidirectional"))
      (node (ref "U$25") (pin "11") (pinfunction "11_11") (pintype "bidirectional"))
    )
    (net (code "12") (name "/DC$12") (class "Default")
      (node (ref "LP$12") (pin "$1") (pinfunction "IN_$1") (pintype "bidirectional"))
      (node (ref "U$25") (pin "12") (pinfunction "12_12") (pintype "bidirectional"))
    )
    (net (code "13") (name "/DC$13") (class "Default")
      (node (ref "LP$13") (pin "$1") (pinfunction "IN_$1") (pintype "bidirectional"))
      (node (ref "U$25") (pin "13") (pinfunction "13_13") (pintype "bidirectional"))
    )
    (net (code "14") (name "/DC$14") (class "Default")
      (node (ref "LP$14") (pin "$1") (pinfunction "IN_$1") (pintype "bidirectional"))
      (node (ref "U$25") (pin "14") (pinfunction "14_14") (pintype "bidirectional"))
    )
    (net (code "15") (name "/DC$15") (class "Default")
      (node (ref "LP$15") (pin "$1") (pinfunction "IN_$1") (pintype "bidirectional"))
      (node (ref "U$25") (pin "15") (pinfunction "15_15") (pintype "bidirectional"))
    )
    (net (code "16") (name "/DC$16") (class "Default")
      (node (ref "LP$16") (pin "$1") (pinfunction "IN_$1") (pintype "bidirectional"))
      (node (ref "U$25") (pin "16") (pinfunction "16_16") (pintype "bidirectional"))
    )
    (net (code "17") (name "/DC$17") (class "Default")
      (node (ref "LP$17") (pin "$1") (pinfunction "IN_$1") (pintype "bidirectional"))
      (node (ref "U$25") (pin "17") (pinfunction "17_17") (pintype "bidirectional"))
    )
    (net (code "18") (name "/DC$18") (class "Default")
      (node (ref "LP$18") (pin "$1") (pinfunction "IN_$1") (pintype "bidirectional"))
      (node (ref "U$25") (pin "18") (pinfunction "18_18") (pintype "bidirectional"))
    )
    (net (code "19") (name "/DC$19") (class "Default")
      (node (ref "LP$19") (pin "$1") (pinfunction "IN_$1") (pintype "bidirectional"))
      (node (ref "U$25") (pin "19") (pinfunction "19_19") (pintype "bidirectional"))
    )
    (net (code "20") (name "/DC$20") (class "Default")
      (node (ref "LP$20") (pin "$1") (pinfunction "IN_$1") (pintype "bidirectional"))
      (node (ref "U$25") (pin "20") (pinfunction "20_20") (pintype "bidirectional"))
    )
    (net (code "21") (name "/DC$21") (class "Default")
      (node (ref "LP$21") (pin "$1") (pinfunction "IN_$1") (pintype "bidirectional"))
      (node (ref "U$25") (pin "21") (pinfunction "21_21") (pintype "bidirectional"))
    )
    (net (code "22") (name "/DC$22") (class "Default")
      (node (ref "LP$22") (pin "$1") (pinfunction "IN_$1") (pintype "bidirectional"))
      (node (ref "U$25") (pin "22") (pinfunction "22_22") (pintype "bidirectional"))
    )
    (net (code "23") (name "/DC$23") (class "Default")
      (node (ref "LP$23") (pin "$1") (pinfunction "IN_$1") (pintype "bidirectional"))
      (node (ref "U$25") (pin "23") (pinfunction "23_23") (pintype "bidirectional"))
    )
    (net (code "24") (name "/DC$24") (class "Default")
      (node (ref "LP$24") (pin "$1") (pinfunction "IN_$1") (pintype "bidirectional"))
      (node (ref "U$25") (pin "24") (pinfunction "24_24") (pintype "bidirectional"))
    )
    (net (code "25") (name "/DC$25") (class "Default")
      (node (ref "LP$25") (pin "$1") (pinfunction "IN_$1") (pintype "bidirectional"))
      (node (ref "U$25") (pin "25") (pinfunction "25_25") (pintype "bidirectional"))
    )
    (net (code "26") (name "/DC$26") (class "Default")
      (node (ref "LP$26") (pin "$1") (pinfunction "IN_$1") (pintype "bidirectional"))
      (node (ref "U$25") (pin "26") (pinfunction "26_26") (pintype "bidirectional"))
    )
    (net (code "27") (name "/DC$27") (class "Default")
      (node (ref "LP$27") (pin "$1") (pinfunction "IN_$1") (pintype "bidirectional"))
      (node (ref "U$25") (pin "27") (pinfunction "27_27") (pintype "bidirectional"))
    )
    (net (code "28") (name "/DC$28") (class "Default")
      (node (ref "LP$28") (pin "$1") (pinfunction "IN_$1") (pintype "bidirectional"))
      (node (ref "U$25") (pin "28") (pinfunction "28_28") (pintype "bidirectional"))
    )
    (net (code "29") (name "/DC$29") (class "Default")
      (node (ref "LP$29") (pin "$1") (pinfunction "IN_$1") (pintype "bidirectional"))
      (node (ref "U$25") (pin "29") (pinfunction "29_29") (pintype "bidirectional"))
    )
    (net (code "30") (name "/DC$30") (class "Default")
      (node (ref "LP$30") (pin "$1") (pinfunction "IN_$1") (pintype "bidirectional"))
      (node (ref "U$25") (pin "30") (pinfunction "30_30") (pintype "bidirectional"))
    )
    (net (code "31") (name "/DC$31") (class "Default")
      (node (ref "LP$31") (pin "$1") (pinfunction "IN_$1") (pintype "bidirectional"))
      (node (ref "U$25") (pin "31") (pinfunction "31_31") (pintype "bidirectional"))
    )
    (net (code "32") (name "/DC$32") (class "Default")
      (node (ref "LP$32") (pin "$1") (pinfunction "IN_$1") (pintype "bidirectional"))
      (node (ref "U$25") (pin "32") (pinfunction "32_32") (pintype "bidirectional"))
    )
    (net (code "33") (name "/DC$33") (class "Default")
      (node (ref "LP$33") (pin "$1") (pinfunction "IN_$1") (pintype "bidirectional"))
      (node (ref "U$25") (pin "33") (pinfunction "33_33") (pintype "bidirectional"))
    )
    (net (code "34") (name "/DC$34") (class "Default")
      (node (ref "LP$34") (pin "$1") (pinfunction "IN_$1") (pintype "bidirectional"))
      (node (ref "U$25") (pin "34") (pinfunction "34_34") (pintype "bidirectional"))
    )
    (net (code "35") (name "/DC$35") (class "Default")
      (node (ref "LP$35") (pin "$1") (pinfunction "IN_$1") (pintype "bidirectional"))
      (node (ref "U$25") (pin "35") (pinfunction "35_35") (pintype "bidirectional"))
    )
    (net (code "36") (name "/DC$36") (class "Default")
      (node (ref "LP$36") (pin "$1") (pinfunction "IN_$1") (pintype "bidirectional"))
      (node (ref "U$25") (pin "36") (pinfunction "36_36") (pintype "bidirectional"))
    )
    (net (code "37") (name "/DC$37") (class "Default")
      (node (ref "LP$37") (pin "$1") (pinfunction "IN_$1") (pintype "bidirectional"))
      (node (ref "U$25") (pin "37") (pinfunction "37_37") (pintype "bidirectional"))
    )
    (net (code "38") (name "/DC$38") (class "Default")
      (node (ref "LP$38") (pin "$1") (pinfunction "IN_$1") (pintype "bidirectional"))
      (node (ref "U$25") (pin "38") (pinfunction "38_38") (pintype "bidirectional"))
    )
    (net (code "39") (name "/DC$39") (class "Default")
      (node (ref "LP$39") (pin "$1") (pinfunction "IN_$1") (pintype "bidirectional"))
      (node (ref "U$25") (pin "39") (pinfunction "39_39") (pintype "bidirectional"))
    )
    (net (code "40") (name "/DC$40") (class "Default")
      (node (ref "LP$40") (pin "$1") (pinfunction "IN_$1") (pintype "bidirectional"))
      (node (ref "U$25") (pin "40") (pinfunction "40_40") (pintype "bidirectional"))
    )
    (net (code "41") (name "/DC$41") (class "Default")
      (node (ref "LP$41") (pin "$1") (pinfunction "IN_$1") (pintype "bidirectional"))
      (node (ref "U$25") (pin "41") (pinfunction "41_41") (pintype "bidirectional"))
    )
    (net (code "42") (name "/DC$42") (class "Default")
      (node (ref "LP$42") (pin "$1") (pinfunction "IN_$1") (pintype "bidirectional"))
      (node (ref "U$25") (pin "42") (pinfunction "42_42") (pintype "bidirectional"))
    )
    (net (code "43") (name "/DC$43") (class "Default")
      (node (ref "LP$43") (pin "$1") (pinfunction "IN_$1") (pintype "bidirectional"))
      (node (ref "U$25") (pin "43") (pinfunction "43_43") (pintype "bidirectional"))
    )
    (net (code "44") (name "/DC$44") (class "Default")
      (node (ref "LP$44") (pin "$1") (pinfunction "IN_$1") (pintype "bidirectional"))
      (node (ref "U$25") (pin "44") (pinfunction "44_44") (pintype "bidirectional"))
    )
    (net (code "45") (name "/DC$45") (class "Default")
      (node (ref "LP$45") (pin "$1") (pinfunction "IN_$1") (pintype "bidirectional"))
      (node (ref "U$25") (pin "45") (pinfunction "45_45") (pintype "bidirectional"))
    )
    (net (code "46") (name "/DC$46") (class "Default")
      (node (ref "LP$46") (pin "$1") (pinfunction "IN_$1") (pintype "bidirectional"))
      (node (ref "U$25") (pin "46") (pinfunction "46_46") (pintype "bidirectional"))
    )
    (net (code "47") (name "/DC$47") (class "Default")
      (node (ref "LP$47") (pin "$1") (pinfunction "IN_$1") (pintype "bidirectional"))
      (node (ref "U$25") (pin "47") (pinfunction "47_47") (pintype "bidirectional"))
    )
    (net (code "48") (name "/DC$48") (class "Default")
      (node (ref "LP$48") (pin "$1") (pinfunction "IN_$1") (pintype "bidirectional"))
      (node (ref "U$25") (pin "48") (pinfunction "48_48") (pintype "bidirectional"))
    )
    (net (code "49") (name "/DCF$01") (class "Default")
      (node (ref "LP$1") (pin "$4") (pinfunction "OUT_$4") (pintype "bidirectional"))
      (node (ref "U$1") (pin "DC§1") (pinfunction "DC§01_DC§1") (pintype "bidirectional"))
      (node (ref "U$11") (pin "OUT1") (pinfunction "2_OUT1") (pintype "passive"))
      (node (ref "U$12") (pin "OUT") (pinfunction "2_OUT") (pintype "passive"))
      (node (ref "U$42") (pin "OUT") (pinfunction "2_OUT") (pintype "passive"))
    )
    (net (code "50") (name "/DCF$02") (class "Default")
      (node (ref "LP$2") (pin "$4") (pinfunction "OUT_$4") (pintype "bidirectional"))
      (node (ref "U$1") (pin "DC§2") (pinfunction "DC§02_DC§2") (pintype "bidirectional"))
      (node (ref "U$43") (pin "OUT") (pinfunction "2_OUT") (pintype "passive"))
    )
    (net (code "51") (name "/DCF$03") (class "Default")
      (node (ref "B$6") (pin "LF") (pinfunction "LF_LF") (pintype "bidirectional"))
      (node (ref "LP$3") (pin "$4") (pinfunction "OUT_$4") (pintype "bidirectional"))
      (node (ref "U$1") (pin "DC§3") (pinfunction "DC§03_DC§3") (pintype "bidirectional"))
      (node (ref "U$44") (pin "OUT") (pinfunction "2_OUT") (pintype "passive"))
    )
    (net (code "52") (name "/DCF$04") (class "Default")
      (node (ref "B$11") (pin "LF") (pinfunction "LF_LF") (pintype "bidirectional"))
      (node (ref "LP$4") (pin "$4") (pinfunction "OUT_$4") (pintype "bidirectional"))
      (node (ref "U$1") (pin "DC§4") (pinfunction "DC§04_DC§4") (pintype "bidirectional"))
      (node (ref "U$45") (pin "OUT") (pinfunction "2_OUT") (pintype "passive"))
    )
    (net (code "53") (name "/DCF$05") (class "Default")
      (node (ref "LP$5") (pin "$4") (pinfunction "OUT_$4") (pintype "bidirectional"))
      (node (ref "U$1") (pin "DC§5") (pinfunction "DC§05_DC§5") (pintype "bidirectional"))
      (node (ref "U$46") (pin "OUT") (pinfunction "2_OUT") (pintype "passive"))
    )
    (net (code "54") (name "/DCF$06") (class "Default")
      (node (ref "B$2") (pin "LF") (pinfunction "LF_LF") (pintype "bidirectional"))
      (node (ref "LP$6") (pin "$4") (pinfunction "OUT_$4") (pintype "bidirectional"))
      (node (ref "U$1") (pin "DC§6") (pinfunction "DC§06_DC§6") (pintype "bidirectional"))
      (node (ref "U$47") (pin "OUT") (pinfunction "2_OUT") (pintype "passive"))
    )
    (net (code "55") (name "/DCF$07") (class "Default")
      (node (ref "LP$7") (pin "$4") (pinfunction "OUT_$4") (pintype "bidirectional"))
      (node (ref "U$1") (pin "DC§7") (pinfunction "DC§07_DC§7") (pintype "bidirectional"))
      (node (ref "U$18") (pin "OUT1") (pinfunction "2_OUT1") (pintype "passive"))
      (node (ref "U$19") (pin "OUT") (pinfunction "2_OUT") (pintype "passive"))
      (node (ref "U$48") (pin "OUT") (pinfunction "2_OUT") (pintype "passive"))
    )
    (net (code "56") (name "/DCF$08") (class "Default")
      (node (ref "B$12") (pin "LF") (pinfunction "LF_LF") (pintype "bidirectional"))
      (node (ref "LP$8") (pin "$4") (pinfunction "OUT_$4") (pintype "bidirectional"))
      (node (ref "U$1") (pin "DC§8") (pinfunction "DC§08_DC§8") (pintype "bidirectional"))
      (node (ref "U$49") (pin "OUT") (pinfunction "2_OUT") (pintype "passive"))
    )
    (net (code "57") (name "/DCF$09") (class "Default")
      (node (ref "B$13") (pin "LF") (pinfunction "LF_LF") (pintype "bidirectional"))
      (node (ref "LP$9") (pin "$4") (pinfunction "OUT_$4") (pintype "bidirectional"))
      (node (ref "U$1") (pin "DC§9") (pinfunction "DC§09_DC§9") (pintype "bidirectional"))
      (node (ref "U$50") (pin "OUT") (pinfunction "2_OUT") (pintype "passive"))
    )
    (net (code "58") (name "/DCF$10") (class "Default")
      (node (ref "LP$10") (pin "$4") (pinfunction "OUT_$4") (pintype "bidirectional"))
      (node (ref "U$1") (pin "DC§10") (pinfunction "DC§10_DC§10") (pintype "bidirectional"))
      (node (ref "U$51") (pin "OUT") (pinfunction "2_OUT") (pintype "passive"))
    )
    (net (code "59") (name "/DCF$11") (class "Default")
      (node (ref "LP$11") (pin "$4") (pinfunction "OUT_$4") (pintype "bidirectional"))
      (node (ref "U$1") (pin "DC§11") (pinfunction "DC§11_DC§11") (pintype "bidirectional"))
      (node (ref "U$52") (pin "OUT") (pinfunction "2_OUT") (pintype "passive"))
    )
    (net (code "60") (name "/DCF$12") (class "Default")
      (node (ref "B$3") (pin "LF") (pinfunction "LF_LF") (pintype "bidirectional"))
      (node (ref "LP$12") (pin "$4") (pinfunction "OUT_$4") (pintype "bidirectional"))
      (node (ref "U$1") (pin "DC§12") (pinfunction "DC§12_DC§12") (pintype "bidirectional"))
      (node (ref "U$53") (pin "OUT") (pinfunction "2_OUT") (pintype "passive"))
    )
    (net (code "61") (name "/DCF$13") (class "Default")
      (node (ref "LP$13") (pin "$4") (pinfunction "OUT_$4") (pintype "bidirectional"))
      (node (ref "U$1") (pin "DC§13") (pinfunction "DC§13_DC§13") (pintype "bidirectional"))
      (node (ref "U$23") (pin "OUT1") (pinfunction "2_OUT1") (pintype "passive"))
      (node (ref "U$24") (pin "OUT") (pinfunction "2_OUT") (pintype "passive"))
      (node (ref "U$54") (pin "IN") (pinfunction "1_IN") (pintype "passive"))
    )
    (net (code "62") (name "/DCF$14") (class "Default")
      (node (ref "LP$14") (pin "$4") (pinfunction "OUT_$4") (pintype "bidirectional"))
      (node (ref "U$1") (pin "DC§14") (pinfunction "DC§14_DC§14") (pintype "bidirectional"))
      (node (ref "U$55") (pin "IN") (pinfunction "1_IN") (pintype "passive"))
    )
    (net (code "63") (name "/DCF$15") (class "Default")
      (node (ref "B$14") (pin "LF") (pinfunction "LF_LF") (pintype "bidirectional"))
      (node (ref "LP$15") (pin "$4") (pinfunction "OUT_$4") (pintype "bidirectional"))
      (node (ref "U$1") (pin "DC§15") (pinfunction "DC§15_DC§15") (pintype "bidirectional"))
      (node (ref "U$56") (pin "IN") (pinfunction "1_IN") (pintype "passive"))
    )
    (net (code "64") (name "/DCF$16") (class "Default")
      (node (ref "B$15") (pin "LF") (pinfunction "LF_LF") (pintype "bidirectional"))
      (node (ref "LP$16") (pin "$4") (pinfunction "OUT_$4") (pintype "bidirectional"))
      (node (ref "U$1") (pin "DC§16") (pinfunction "DC§16_DC§16") (pintype "bidirectional"))
      (node (ref "U$57") (pin "IN") (pinfunction "1_IN") (pintype "passive"))
    )
    (net (code "65") (name "/DCF$17") (class "Default")
      (node (ref "LP$17") (pin "$4") (pinfunction "OUT_$4") (pintype "bidirectional"))
      (node (ref "U$1") (pin "DC§17") (pinfunction "DC§17_DC§17") (pintype "bidirectional"))
      (node (ref "U$58") (pin "IN") (pinfunction "1_IN") (pintype "passive"))
    )
    (net (code "66") (name "/DCF$18") (class "Default")
      (node (ref "B$4") (pin "LF") (pinfunction "LF_LF") (pintype "bidirectional"))
      (node (ref "LP$18") (pin "$4") (pinfunction "OUT_$4") (pintype "bidirectional"))
      (node (ref "U$1") (pin "DC§18") (pinfunction "DC§18_DC§18") (pintype "bidirectional"))
      (node (ref "U$59") (pin "IN") (pinfunction "1_IN") (pintype "passive"))
    )
    (net (code "67") (name "/DCF$19") (class "Default")
      (node (ref "LP$19") (pin "$4") (pinfunction "OUT_$4") (pintype "bidirectional"))
      (node (ref "U$1") (pin "DC§19") (pinfunction "DC§019_DC§19") (pintype "bidirectional"))
      (node (ref "U$27") (pin "OUT1") (pinfunction "2_OUT1") (pintype "passive"))
      (node (ref "U$28") (pin "OUT") (pinfunction "2_OUT") (pintype "passive"))
      (node (ref "U$60") (pin "IN") (pinfunction "1_IN") (pintype "passive"))
    )
    (net (code "68") (name "/DCF$20") (class "Default")
      (node (ref "B$16") (pin "LF") (pinfunction "LF_LF") (pintype "bidirectional"))
      (node (ref "LP$20") (pin "$4") (pinfunction "OUT_$4") (pintype "bidirectional"))
      (node (ref "U$1") (pin "DC§20") (pinfunction "DC§20_DC§20") (pintype "bidirectional"))
      (node (ref "U$61") (pin "IN") (pinfunction "1_IN") (pintype "passive"))
    )
    (net (code "69") (name "/DCF$21") (class "Default")
      (node (ref "B$17") (pin "LF") (pinfunction "LF_LF") (pintype "bidirectional"))
      (node (ref "LP$21") (pin "$4") (pinfunction "OUT_$4") (pintype "bidirectional"))
      (node (ref "U$1") (pin "DC§21") (pinfunction "DC§21_DC§21") (pintype "bidirectional"))
      (node (ref "U$62") (pin "IN") (pinfunction "1_IN") (pintype "passive"))
    )
    (net (code "70") (name "/DCF$22") (class "Default")
      (node (ref "LP$22") (pin "$4") (pinfunction "OUT_$4") (pintype "bidirectional"))
      (node (ref "U$1") (pin "DC§22") (pinfunction "DC§22_DC§22") (pintype "bidirectional"))
      (node (ref "U$63") (pin "IN") (pinfunction "1_IN") (pintype "passive"))
    )
    (net (code "71") (name "/DCF$23") (class "Default")
      (node (ref "LP$23") (pin "$4") (pinfunction "OUT_$4") (pintype "bidirectional"))
      (node (ref "U$1") (pin "DC§23") (pinfunction "DC§23_DC§23") (pintype "bidirectional"))
      (node (ref "U$64") (pin "IN") (pinfunction "1_IN") (pintype "passive"))
    )
    (net (code "72") (name "/DCF$24") (class "Default")
      (node (ref "B$5") (pin "LF") (pinfunction "LF_LF") (pintype "bidirectional"))
      (node (ref "LP$24") (pin "$4") (pinfunction "OUT_$4") (pintype "bidirectional"))
      (node (ref "U$1") (pin "DC§24") (pinfunction "DC§24_DC§24") (pintype "bidirectional"))
      (node (ref "U$65") (pin "IN") (pinfunction "1_IN") (pintype "passive"))
    )
    (net (code "73") (name "/DCF$25") (class "Default")
      (node (ref "LP$25") (pin "$4") (pinfunction "OUT_$4") (pintype "bidirectional"))
      (node (ref "U$1") (pin "DC§25") (pinfunction "DC§025_DC§25") (pintype "bidirectional"))
      (node (ref "U$31") (pin "OUT1") (pinfunction "2_OUT1") (pintype "passive"))
      (node (ref "U$32") (pin "OUT") (pinfunction "2_OUT") (pintype "passive"))
      (node (ref "U$66") (pin "IN") (pinfunction "1_IN") (pintype "passive"))
    )
    (net (code "74") (name "/DCF$26") (class "Default")
      (node (ref "LP$26") (pin "$4") (pinfunction "OUT_$4") (pintype "bidirectional"))
      (node (ref "U$1") (pin "DC§26") (pinfunction "DC§026_DC§26") (pintype "bidirectional"))
      (node (ref "U$67") (pin "IN") (pinfunction "1_IN") (pintype "passive"))
    )
    (net (code "75") (name "/DCF$27") (class "Default")
      (node (ref "B$10") (pin "LF") (pinfunction "LF_LF") (pintype "bidirectional"))
      (node (ref "LP$27") (pin "$4") (pinfunction "OUT_$4") (pintype "bidirectional"))
      (node (ref "U$1") (pin "DC§27") (pinfunction "DC§027_DC§27") (pintype "bidirectional"))
      (node (ref "U$68") (pin "IN") (pinfunction "1_IN") (pintype "passive"))
    )
    (net (code "76") (name "/DCF$28") (class "Default")
      (node (ref "B$18") (pin "LF") (pinfunction "LF_LF") (pintype "bidirectional"))
      (node (ref "LP$28") (pin "$4") (pinfunction "OUT_$4") (pintype "bidirectional"))
      (node (ref "U$1") (pin "DC§28") (pinfunction "DC§028_DC§28") (pintype "bidirectional"))
      (node (ref "U$69") (pin "IN") (pinfunction "1_IN") (pintype "passive"))
    )
    (net (code "77") (name "/DCF$29") (class "Default")
      (node (ref "LP$29") (pin "$4") (pinfunction "OUT_$4") (pintype "bidirectional"))
      (node (ref "U$1") (pin "DC§29") (pinfunction "DC§029_DC§29") (pintype "bidirectional"))
      (node (ref "U$70") (pin "IN") (pinfunction "1_IN") (pintype "passive"))
    )
    (net (code "78") (name "/DCF$30") (class "Default")
      (node (ref "B$8") (pin "LF") (pinfunction "LF_LF") (pintype "bidirectional"))
      (node (ref "LP$30") (pin "$4") (pinfunction "OUT_$4") (pintype "bidirectional"))
      (node (ref "U$1") (pin "DC§30") (pinfunction "DC§030_DC§30") (pintype "bidirectional"))
      (node (ref "U$71") (pin "IN") (pinfunction "1_IN") (pintype "passive"))
    )
    (net (code "79") (name "/DCF$31") (class "Default")
      (node (ref "LP$31") (pin "$4") (pinfunction "OUT_$4") (pintype "bidirectional"))
      (node (ref "U$1") (pin "DC§31") (pinfunction "DC§031_DC§31") (pintype "bidirectional"))
      (node (ref "U$35") (pin "OUT1") (pinfunction "2_OUT1") (pintype "passive"))
      (node (ref "U$36") (pin "OUT") (pinfunction "2_OUT") (pintype "passive"))
      (node (ref "U$72") (pin "IN") (pinfunction "1_IN") (pintype "passive"))
    )
    (net (code "80") (name "/DCF$32") (class "Default")
      (node (ref "B$19") (pin "LF") (pinfunction "LF_LF") (pintype "bidirectional"))
      (node (ref "LP$32") (pin "$4") (pinfunction "OUT_$4") (pintype "bidirectional"))
      (node (ref "U$1") (pin "DC§32") (pinfunction "DC§032_DC§32") (pintype "bidirectional"))
      (node (ref "U$73") (pin "IN") (pinfunction "1_IN") (pintype "passive"))
    )
    (net (code "81") (name "/DCF$33") (class "Default")
      (node (ref "B$20") (pin "LF") (pinfunction "LF_LF") (pintype "bidirectional"))
      (node (ref "LP$33") (pin "$4") (pinfunction "OUT_$4") (pintype "bidirectional"))
      (node (ref "U$1") (pin "DC§33") (pinfunction "DC§033_DC§33") (pintype "bidirectional"))
      (node (ref "U$74") (pin "IN") (pinfunction "1_IN") (pintype "passive"))
    )
    (net (code "82") (name "/DCF$34") (class "Default")
      (node (ref "LP$34") (pin "$4") (pinfunction "OUT_$4") (pintype "bidirectional"))
      (node (ref "U$1") (pin "DC§34") (pinfunction "DC§034_DC§34") (pintype "bidirectional"))
      (node (ref "U$75") (pin "IN") (pinfunction "1_IN") (pintype "passive"))
    )
    (net (code "83") (name "/DCF$35") (class "Default")
      (node (ref "LP$35") (pin "$4") (pinfunction "OUT_$4") (pintype "bidirectional"))
      (node (ref "U$1") (pin "DC§35") (pinfunction "DC§035_DC§35") (pintype "bidirectional"))
      (node (ref "U$76") (pin "IN") (pinfunction "1_IN") (pintype "passive"))
    )
    (net (code "84") (name "/DCF$36") (class "Default")
      (node (ref "B$9") (pin "LF") (pinfunction "LF_LF") (pintype "bidirectional"))
      (node (ref "LP$36") (pin "$4") (pinfunction "OUT_$4") (pintype "bidirectional"))
      (node (ref "U$1") (pin "DC§36") (pinfunction "DC§036_DC§36") (pintype "bidirectional"))
      (node (ref "U$77") (pin "IN") (pinfunction "1_IN") (pintype "passive"))
    )
    (net (code "85") (name "/DCF$37") (class "Default")
      (node (ref "LP$37") (pin "$4") (pinfunction "OUT_$4") (pintype "bidirectional"))
      (node (ref "U$1") (pin "DC§37") (pinfunction "DC§037_DC§37") (pintype "bidirectional"))
      (node (ref "U$39") (pin "OUT1") (pinfunction "2_OUT1") (pintype "passive"))
      (node (ref "U$40") (pin "OUT") (pinfunction "2_OUT") (pintype "passive"))
      (node (ref "U$78") (pin "IN") (pinfunction "1_IN") (pintype "passive"))
    )
    (net (code "86") (name "/DCF$38") (class "Default")
      (node (ref "LP$38") (pin "$4") (pinfunction "OUT_$4") (pintype "bidirectional"))
      (node (ref "U$1") (pin "DC§38") (pinfunction "DC§038_DC§38") (pintype "bidirectional"))
      (node (ref "U$79") (pin "IN") (pinfunction "1_IN") (pintype "passive"))
    )
    (net (code "87") (name "/DCF$39") (class "Default")
      (node (ref "B$21") (pin "LF") (pinfunction "LF_LF") (pintype "bidirectional"))
      (node (ref "LP$39") (pin "$4") (pinfunction "OUT_$4") (pintype "bidirectional"))
      (node (ref "U$1") (pin "DC§39") (pinfunction "DC§039_DC§39") (pintype "bidirectional"))
      (node (ref "U$80") (pin "IN") (pinfunction "1_IN") (pintype "passive"))
    )
    (net (code "88") (name "/DCF$40") (class "Default")
      (node (ref "B$22") (pin "LF") (pinfunction "LF_LF") (pintype "bidirectional"))
      (node (ref "LP$40") (pin "$4") (pinfunction "OUT_$4") (pintype "bidirectional"))
      (node (ref "U$1") (pin "DC§40") (pinfunction "DC§040_DC§40") (pintype "bidirectional"))
      (node (ref "U$81") (pin "IN") (pinfunction "1_IN") (pintype "passive"))
    )
    (net (code "89") (name "/DCF$41") (class "Default")
      (node (ref "LP$41") (pin "$4") (pinfunction "OUT_$4") (pintype "bidirectional"))
      (node (ref "U$1") (pin "DC§41") (pinfunction "DC§041_DC§41") (pintype "bidirectional"))
      (node (ref "U$82") (pin "IN") (pinfunction "1_IN") (pintype "passive"))
    )
    (net (code "90") (name "/DCF$42") (class "Default")
      (node (ref "B$7") (pin "LF") (pinfunction "LF_LF") (pintype "bidirectional"))
      (node (ref "LP$42") (pin "$4") (pinfunction "OUT_$4") (pintype "bidirectional"))
      (node (ref "U$1") (pin "DC§42") (pinfunction "DC§042_DC§42") (pintype "bidirectional"))
      (node (ref "U$83") (pin "IN") (pinfunction "1_IN") (pintype "passive"))
    )
    (net (code "91") (name "/DCF$43") (class "Default")
      (node (ref "LP$43") (pin "$4") (pinfunction "OUT_$4") (pintype "bidirectional"))
      (node (ref "U$1") (pin "DC§43") (pinfunction "DC§043_DC§43") (pintype "bidirectional"))
      (node (ref "U$14") (pin "OUT1") (pinfunction "2_OUT1") (pintype "passive"))
      (node (ref "U$15") (pin "OUT") (pinfunction "2_OUT") (pintype "passive"))
      (node (ref "U$84") (pin "IN") (pinfunction "1_IN") (pintype "passive"))
    )
    (net (code "92") (name "/DCF$44") (class "Default")
      (node (ref "B$23") (pin "LF") (pinfunction "LF_LF") (pintype "bidirectional"))
      (node (ref "LP$44") (pin "$4") (pinfunction "OUT_$4") (pintype "bidirectional"))
      (node (ref "U$1") (pin "DC§44") (pinfunction "DC§044_DC§44") (pintype "bidirectional"))
      (node (ref "U$85") (pin "IN") (pinfunction "1_IN") (pintype "passive"))
    )
    (net (code "93") (name "/DCF$45") (class "Default")
      (node (ref "B$24") (pin "LF") (pinfunction "LF_LF") (pintype "bidirectional"))
      (node (ref "LP$45") (pin "$4") (pinfunction "OUT_$4") (pintype "bidirectional"))
      (node (ref "U$1") (pin "DC§45") (pinfunction "DC§045_DC§45") (pintype "bidirectional"))
      (node (ref "U$86") (pin "IN") (pinfunction "1_IN") (pintype "passive"))
    )
    (net (code "94") (name "/DCF$46") (class "Default")
      (node (ref "LP$46") (pin "$4") (pinfunction "OUT_$4") (pintype "bidirectional"))
      (node (ref "U$1") (pin "DC§46") (pinfunction "DC§046_DC§46") (pintype "bidirectional"))
      (node (ref "U$87") (pin "IN") (pinfunction "1_IN") (pintype "passive"))
    )
    (net (code "95") (name "/DCF$47") (class "Default")
      (node (ref "LP$47") (pin "$4") (pinfunction "OUT_$4") (pintype "bidirectional"))
      (node (ref "U$1") (pin "DC§47") (pinfunction "DC§047_DC§47") (pintype "bidirectional"))
      (node (ref "U$88") (pin "IN") (pinfunction "1_IN") (pintype "passive"))
    )
    (net (code "96") (name "/DCF$48") (class "Default")
      (node (ref "B$1") (pin "LF") (pinfunction "LF_LF") (pintype "bidirectional"))
      (node (ref "LP$48") (pin "$4") (pinfunction "OUT_$4") (pintype "bidirectional"))
      (node (ref "U$1") (pin "DC§48") (pinfunction "DC§048_DC§48") (pintype "bidirectional"))
      (node (ref "U$89") (pin "IN") (pinfunction "1_IN") (pintype "passive"))
    )
    (net (code "97") (name "/RF$R1") (class "Default")
      (node (ref "L$3") (pin "OUT") (pinfunction "OUT_OUT") (pintype "passive"))
      (node (ref "U$1") (pin "RF$06_R1") (pinfunction "RF$06_R1_RF$06_R1") (pintype "bidirectional"))
      (node (ref "U$18") (pin "OUT") (pinfunction "1_OUT") (pintype "passive"))
    )
    (net (code "98") (name "/RF$R2") (class "Default")
      (node (ref "L$4") (pin "OUT") (pinfunction "OUT_OUT") (pintype "passive"))
      (node (ref "U$1") (pin "RF$12_R2") (pinfunction "RF$12_R2_RF$12_R2") (pintype "bidirectional"))
      (node (ref "U$23") (pin "OUT") (pinfunction "1_OUT") (pintype "passive"))
    )
    (net (code "99") (name "/RF$R3") (class "Default")
      (node (ref "L$5") (pin "OUT") (pinfunction "OUT_OUT") (pintype "passive"))
      (node (ref "U$1") (pin "RF$18_R3") (pinfunction "RF$18_R3_RF$18_R3") (pintype "bidirectional"))
      (node (ref "U$27") (pin "OUT") (pinfunction "1_OUT") (pintype "passive"))
    )
    (net (code "100") (name "/RF$R4") (class "Default")
      (node (ref "L$6") (pin "OUT") (pinfunction "OUT_OUT") (pintype "passive"))
      (node (ref "U$1") (pin "RF$24_R4") (pinfunction "RF$24_R4_RF$24_R4") (pintype "bidirectional"))
      (node (ref "U$31") (pin "OUT") (pinfunction "1_OUT") (pintype "passive"))
    )
    (net (code "101") (name "/RF$R5") (class "Default")
      (node (ref "L$7") (pin "OUT") (pinfunction "OUT_OUT") (pintype "passive"))
      (node (ref "U$1") (pin "RF$30_R5") (pinfunction "RF$30_R5_RF$30_R5") (pintype "bidirectional"))
      (node (ref "U$35") (pin "OUT") (pinfunction "1_OUT") (pintype "passive"))
    )
    (net (code "102") (name "/RF$R6") (class "Default")
      (node (ref "L$8") (pin "OUT") (pinfunction "OUT_OUT") (pintype "passive"))
      (node (ref "U$1") (pin "RF$36_R6") (pinfunction "RF$36_R6_RF$36_R6") (pintype "bidirectional"))
      (node (ref "U$39") (pin "OUT") (pinfunction "1_OUT") (pintype "passive"))
    )
    (net (code "103") (name "/RF$R7") (class "Default")
      (node (ref "L$1") (pin "OUT") (pinfunction "OUT_OUT") (pintype "passive"))
      (node (ref "U$1") (pin "RF$42_R7") (pinfunction "RF$42_R7_RF$42_R7") (pintype "bidirectional"))
      (node (ref "U$14") (pin "OUT") (pinfunction "1_OUT") (pintype "passive"))
    )
    (net (code "104") (name "/RF$R8") (class "Default")
      (node (ref "L$2") (pin "OUT") (pinfunction "OUT_OUT") (pintype "passive"))
      (node (ref "U$1") (pin "RF$48_R8") (pinfunction "RF$48_R8_RF$48_R8") (pintype "bidirectional"))
      (node (ref "U$11") (pin "OUT") (pinfunction "1_OUT") (pintype "passive"))
    )
    (net (code "105") (name "GND") (class "Default")
      (node (ref "LP$1") (pin "$6") (pinfunction "GND_$6") (pintype "bidirectional"))
      (node (ref "LP$10") (pin "$6") (pinfunction "GND_$6") (pintype "bidirectional"))
      (node (ref "LP$11") (pin "$6") (pinfunction "GND_$6") (pintype "bidirectional"))
      (node (ref "LP$12") (pin "$6") (pinfunction "GND_$6") (pintype "bidirectional"))
      (node (ref "LP$13") (pin "$6") (pinfunction "GND_$6") (pintype "bidirectional"))
      (node (ref "LP$14") (pin "$6") (pinfunction "GND_$6") (pintype "bidirectional"))
      (node (ref "LP$15") (pin "$6") (pinfunction "GND_$6") (pintype "bidirectional"))
      (node (ref "LP$16") (pin "$6") (pinfunction "GND_$6") (pintype "bidirectional"))
      (node (ref "LP$17") (pin "$6") (pinfunction "GND_$6") (pintype "bidirectional"))
      (node (ref "LP$18") (pin "$6") (pinfunction "GND_$6") (pintype "bidirectional"))
      (node (ref "LP$19") (pin "$6") (pinfunction "GND_$6") (pintype "bidirectional"))
      (node (ref "LP$2") (pin "$6") (pinfunction "GND_$6") (pintype "bidirectional"))
      (node (ref "LP$20") (pin "$6") (pinfunction "GND_$6") (pintype "bidirectional"))
      (node (ref "LP$21") (pin "$6") (pinfunction "GND_$6") (pintype "bidirectional"))
      (node (ref "LP$22") (pin "$6") (pinfunction "GND_$6") (pintype "bidirectional"))
      (node (ref "LP$23") (pin "$6") (pinfunction "GND_$6") (pintype "bidirectional"))
      (node (ref "LP$24") (pin "$6") (pinfunction "GND_$6") (pintype "bidirectional"))
      (node (ref "LP$25") (pin "$6") (pinfunction "GND_$6") (pintype "bidirectional"))
      (node (ref "LP$26") (pin "$6") (pinfunction "GND_$6") (pintype "bidirectional"))
      (node (ref "LP$27") (pin "$6") (pinfunction "GND_$6") (pintype "bidirectional"))
      (node (ref "LP$28") (pin "$6") (pinfunction "GND_$6") (pintype "bidirectional"))
      (node (ref "LP$29") (pin "$6") (pinfunction "GND_$6") (pintype "bidirectional"))
      (node (ref "LP$3") (pin "$6") (pinfunction "GND_$6") (pintype "bidirectional"))
      (node (ref "LP$30") (pin "$6") (pinfunction "GND_$6") (pintype "bidirectional"))
      (node (ref "LP$31") (pin "$6") (pinfunction "GND_$6") (pintype "bidirectional"))
      (node (ref "LP$32") (pin "$6") (pinfunction "GND_$6") (pintype "bidirectional"))
      (node (ref "LP$33") (pin "$6") (pinfunction "GND_$6") (pintype "bidirectional"))
      (node (ref "LP$34") (pin "$6") (pinfunction "GND_$6") (pintype "bidirectional"))
      (node (ref "LP$35") (pin "$6") (pinfunction "GND_$6") (pintype "bidirectional"))
      (node (ref "LP$36") (pin "$6") (pinfunction "GND_$6") (pintype "bidirectional"))
      (node (ref "LP$37") (pin "$6") (pinfunction "GND_$6") (pintype "bidirectional"))
      (node (ref "LP$38") (pin "$6") (pinfunction "GND_$6") (pintype "bidirectional"))
      (node (ref "LP$39") (pin "$6") (pinfunction "GND_$6") (pintype "bidirectional"))
      (node (ref "LP$4") (pin "$6") (pinfunction "GND_$6") (pintype "bidirectional"))
      (node (ref "LP$40") (pin "$6") (pinfunction "GND_$6") (pintype "bidirectional"))
      (node (ref "LP$41") (pin "$6") (pinfunction "GND_$6") (pintype "bidirectional"))
      (node (ref "LP$42") (pin "$6") (pinfunction "GND_$6") (pintype "bidirectional"))
      (node (ref "LP$43") (pin "$6") (pinfunction "GND_$6") (pintype "bidirectional"))
      (node (ref "LP$44") (pin "$6") (pinfunction "GND_$6") (pintype "bidirectional"))
      (node (ref "LP$45") (pin "$6") (pinfunction "GND_$6") (pintype "bidirectional"))
      (node (ref "LP$46") (pin "$6") (pinfunction "GND_$6") (pintype "bidirectional"))
      (node (ref "LP$47") (pin "$6") (pinfunction "GND_$6") (pintype "bidirectional"))
      (node (ref "LP$48") (pin "$6") (pinfunction "GND_$6") (pintype "bidirectional"))
      (node (ref "LP$5") (pin "$6") (pinfunction "GND_$6") (pintype "bidirectional"))
      (node (ref "LP$6") (pin "$6") (pinfunction "GND_$6") (pintype "bidirectional"))
      (node (ref "LP$7") (pin "$6") (pinfunction "GND_$6") (pintype "bidirectional"))
      (node (ref "LP$8") (pin "$6") (pinfunction "GND_$6") (pintype "bidirectional"))
      (node (ref "LP$9") (pin "$6") (pinfunction "GND_$6") (pintype "bidirectional"))
      (node (ref "S$1") (pin "2@1") (pinfunction "GND_2@1") (pintype "passive"))
      (node (ref "S$1") (pin "2@2") (pinfunction "GND_2@2") (pintype "passive"))
      (node (ref "S$10") (pin "2@1") (pinfunction "GND_2@1") (pintype "passive"))
      (node (ref "S$10") (pin "2@2") (pinfunction "GND_2@2") (pintype "passive"))
      (node (ref "S$11") (pin "2@1") (pinfunction "GND_2@1") (pintype "passive"))
      (node (ref "S$11") (pin "2@2") (pinfunction "GND_2@2") (pintype "passive"))
      (node (ref "S$12") (pin "2@1") (pinfunction "GND_2@1") (pintype "passive"))
      (node (ref "S$12") (pin "2@2") (pinfunction "GND_2@2") (pintype "passive"))
      (node (ref "S$13") (pin "2@1") (pinfunction "GND_2@1") (pintype "passive"))
      (node (ref "S$13") (pin "2@2") (pinfunction "GND_2@2") (pintype "passive"))
      (node (ref "S$14") (pin "2@1") (pinfunction "GND_2@1") (pintype "passive"))
      (node (ref "S$14") (pin "2@2") (pinfunction "GND_2@2") (pintype "passive"))
      (node (ref "S$15") (pin "2@1") (pinfunction "GND_2@1") (pintype "passive"))
      (node (ref "S$15") (pin "2@2") (pinfunction "GND_2@2") (pintype "passive"))
      (node (ref "S$16") (pin "2@1") (pinfunction "GND_2@1") (pintype "passive"))
      (node (ref "S$16") (pin "2@2") (pinfunction "GND_2@2") (pintype "passive"))
      (node (ref "S$17") (pin "2@1") (pinfunction "GND_2@1") (pintype "passive"))
      (node (ref "S$17") (pin "2@2") (pinfunction "GND_2@2") (pintype "passive"))
      (node (ref "S$2") (pin "2@1") (pinfunction "GND_2@1") (pintype "passive"))
      (node (ref "S$2") (pin "2@2") (pinfunction "GND_2@2") (pintype "passive"))
      (node (ref "S$3") (pin "2@1") (pinfunction "GND_2@1") (pintype "passive"))
      (node (ref "S$3") (pin "2@2") (pinfunction "GND_2@2") (pintype "passive"))
      (node (ref "S$4") (pin "2@1") (pinfunction "GND_2@1") (pintype "passive"))
      (node (ref "S$4") (pin "2@2") (pinfunction "GND_2@2") (pintype "passive"))
      (node (ref "S$5") (pin "2@1") (pinfunction "GND_2@1") (pintype "passive"))
      (node (ref "S$5") (pin "2@2") (pinfunction "GND_2@2") (pintype "passive"))
      (node (ref "S$6") (pin "2@1") (pinfunction "GND_2@1") (pintype "passive"))
      (node (ref "S$6") (pin "2@2") (pinfunction "GND_2@2") (pintype "passive"))
      (node (ref "S$7") (pin "2@1") (pinfunction "GND_2@1") (pintype "passive"))
      (node (ref "S$7") (pin "2@2") (pinfunction "GND_2@2") (pintype "passive"))
      (node (ref "S$8") (pin "2@1") (pinfunction "GND_2@1") (pintype "passive"))
      (node (ref "S$8") (pin "2@2") (pinfunction "GND_2@2") (pintype "passive"))
      (node (ref "S$9") (pin "2@1") (pinfunction "GND_2@1") (pintype "passive"))
      (node (ref "S$9") (pin "2@2") (pinfunction "GND_2@2") (pintype "passive"))
      (node (ref "U$10") (pin "OUT") (pinfunction "2_OUT") (pintype "passive"))
      (node (ref "U$12") (pin "IN") (pinfunction "1_IN") (pintype "passive"))
      (node (ref "U$15") (pin "IN") (pinfunction "1_IN") (pintype "passive"))
      (node (ref "U$16") (pin "OUT") (pinfunction "2_OUT") (pintype "passive"))
      (node (ref "U$19") (pin "IN") (pinfunction "1_IN") (pintype "passive"))
      (node (ref "U$21") (pin "OUT") (pinfunction "2_OUT") (pintype "passive"))
      (node (ref "U$22") (pin "OUT") (pinfunction "2_OUT") (pintype "passive"))
      (node (ref "U$24") (pin "IN") (pinfunction "1_IN") (pintype "passive"))
      (node (ref "U$25") (pin "49") (pinfunction "49_49") (pintype "bidirectional"))
      (node (ref "U$25") (pin "50") (pinfunction "50_50") (pintype "bidirectional"))
      (node (ref "U$25") (pin "51") (pinfunction "51_51") (pintype "bidirectional"))
      (node (ref "U$28") (pin "IN") (pinfunction "1_IN") (pintype "passive"))
      (node (ref "U$30") (pin "OUT") (pinfunction "2_OUT") (pintype "passive"))
      (node (ref "U$32") (pin "IN") (pinfunction "1_IN") (pintype "passive"))
      (node (ref "U$34") (pin "OUT") (pinfunction "2_OUT") (pintype "passive"))
      (node (ref "U$36") (pin "IN") (pinfunction "1_IN") (pintype "passive"))
      (node (ref "U$38") (pin "OUT") (pinfunction "2_OUT") (pintype "passive"))
      (node (ref "U$40") (pin "IN") (pinfunction "1_IN") (pintype "passive"))
      (node (ref "U$42") (pin "IN") (pinfunction "1_IN") (pintype "passive"))
      (node (ref "U$43") (pin "IN") (pinfunction "1_IN") (pintype "passive"))
      (node (ref "U$44") (pin "IN") (pinfunction "1_IN") (pintype "passive"))
      (node (ref "U$45") (pin "IN") (pinfunction "1_IN") (pintype "passive"))
      (node (ref "U$46") (pin "IN") (pinfunction "1_IN") (pintype "passive"))
      (node (ref "U$47") (pin "IN") (pinfunction "1_IN") (pintype "passive"))
      (node (ref "U$48") (pin "IN") (pinfunction "1_IN") (pintype "passive"))
      (node (ref "U$49") (pin "IN") (pinfunction "1_IN") (pintype "passive"))
      (node (ref "U$50") (pin "IN") (pinfunction "1_IN") (pintype "passive"))
      (node (ref "U$51") (pin "IN") (pinfunction "1_IN") (pintype "passive"))
      (node (ref "U$52") (pin "IN") (pinfunction "1_IN") (pintype "passive"))
      (node (ref "U$53") (pin "IN") (pinfunction "1_IN") (pintype "passive"))
      (node (ref "U$54") (pin "OUT") (pinfunction "2_OUT") (pintype "passive"))
      (node (ref "U$55") (pin "OUT") (pinfunction "2_OUT") (pintype "passive"))
      (node (ref "U$56") (pin "OUT") (pinfunction "2_OUT") (pintype "passive"))
      (node (ref "U$57") (pin "OUT") (pinfunction "2_OUT") (pintype "passive"))
      (node (ref "U$58") (pin "OUT") (pinfunction "2_OUT") (pintype "passive"))
      (node (ref "U$59") (pin "OUT") (pinfunction "2_OUT") (pintype "passive"))
      (node (ref "U$60") (pin "OUT") (pinfunction "2_OUT") (pintype "passive"))
      (node (ref "U$61") (pin "OUT") (pinfunction "2_OUT") (pintype "passive"))
      (node (ref "U$62") (pin "OUT") (pinfunction "2_OUT") (pintype "passive"))
      (node (ref "U$63") (pin "OUT") (pinfunction "2_OUT") (pintype "passive"))
      (node (ref "U$64") (pin "OUT") (pinfunction "2_OUT") (pintype "passive"))
      (node (ref "U$65") (pin "OUT") (pinfunction "2_OUT") (pintype "passive"))
      (node (ref "U$66") (pin "OUT") (pinfunction "2_OUT") (pintype "passive"))
      (node (ref "U$67") (pin "OUT") (pinfunction "2_OUT") (pintype "passive"))
      (node (ref "U$68") (pin "OUT") (pinfunction "2_OUT") (pintype "passive"))
      (node (ref "U$69") (pin "OUT") (pinfunction "2_OUT") (pintype "passive"))
      (node (ref "U$7") (pin "OUT") (pinfunction "2_OUT") (pintype "passive"))
      (node (ref "U$70") (pin "OUT") (pinfunction "2_OUT") (pintype "passive"))
      (node (ref "U$71") (pin "OUT") (pinfunction "2_OUT") (pintype "passive"))
      (node (ref "U$72") (pin "OUT") (pinfunction "2_OUT") (pintype "passive"))
      (node (ref "U$73") (pin "OUT") (pinfunction "2_OUT") (pintype "passive"))
      (node (ref "U$74") (pin "OUT") (pinfunction "2_OUT") (pintype "passive"))
      (node (ref "U$75") (pin "OUT") (pinfunction "2_OUT") (pintype "passive"))
      (node (ref "U$76") (pin "OUT") (pinfunction "2_OUT") (pintype "passive"))
      (node (ref "U$77") (pin "OUT") (pinfunction "2_OUT") (pintype "passive"))
      (node (ref "U$78") (pin "OUT") (pinfunction "2_OUT") (pintype "passive"))
      (node (ref "U$79") (pin "OUT") (pinfunction "2_OUT") (pintype "passive"))
      (node (ref "U$80") (pin "OUT") (pinfunction "2_OUT") (pintype "passive"))
      (node (ref "U$81") (pin "OUT") (pinfunction "2_OUT") (pintype "passive"))
      (node (ref "U$82") (pin "OUT") (pinfunction "2_OUT") (pintype "passive"))
      (node (ref "U$83") (pin "OUT") (pinfunction "2_OUT") (pintype "passive"))
      (node (ref "U$84") (pin "OUT") (pinfunction "2_OUT") (pintype "passive"))
      (node (ref "U$85") (pin "OUT") (pinfunction "2_OUT") (pintype "passive"))
      (node (ref "U$86") (pin "OUT") (pinfunction "2_OUT") (pintype "passive"))
      (node (ref "U$87") (pin "OUT") (pinfunction "2_OUT") (pintype "passive"))
      (node (ref "U$88") (pin "OUT") (pinfunction "2_OUT") (pintype "passive"))
      (node (ref "U$89") (pin "OUT") (pinfunction "2_OUT") (pintype "passive"))
    )
    (net (code "106") (name "Net-(B$6-PadHF)") (class "Default")
      (node (ref "B$6") (pin "HF") (pinfunction "HF_HF") (pintype "bidirectional"))
      (node (ref "S$1") (pin "1") (pinfunction "1_1") (pintype "passive"))
    )
    (net (code "107") (name "Net-(B$6-PadOUT)") (class "Default")
      (node (ref "B$6") (pin "OUT") (pinfunction "OUT_OUT") (pintype "bidirectional"))
      (node (ref "U$1") (pin "RF$03_G1") (pinfunction "RF$03_G1_RF$03_G1") (pintype "bidirectional"))
    )
    (net (code "108") (name "Net-(B$10-PadHF)") (class "Default")
      (node (ref "B$10") (pin "HF") (pinfunction "HF_HF") (pintype "bidirectional"))
      (node (ref "S$2") (pin "1") (pinfunction "1_1") (pintype "passive"))
    )
    (net (code "109") (name "Net-(B$10-PadOUT)") (class "Default")
      (node (ref "B$10") (pin "OUT") (pinfunction "OUT_OUT") (pintype "bidirectional"))
      (node (ref "U$1") (pin "RF$27_G9") (pinfunction "RF$27_G9_RF$27_G9") (pintype "bidirectional"))
    )
    (net (code "110") (name "Net-(B$11-PadHF)") (class "Default")
      (node (ref "B$11") (pin "HF") (pinfunction "HF_HF") (pintype "bidirectional"))
      (node (ref "S$8") (pin "1") (pinfunction "1_1") (pintype "passive"))
    )
    (net (code "111") (name "Net-(B$11-PadOUT)") (class "Default")
      (node (ref "B$11") (pin "OUT") (pinfunction "OUT_OUT") (pintype "bidirectional"))
      (node (ref "U$1") (pin "RF$04_G2") (pinfunction "RF$04_G2_RF$04_G2") (pintype "bidirectional"))
    )
    (net (code "112") (name "Net-(B$12-PadHF)") (class "Default")
      (node (ref "B$12") (pin "HF") (pinfunction "HF_HF") (pintype "bidirectional"))
      (node (ref "S$9") (pin "1") (pinfunction "1_1") (pintype "passive"))
    )
    (net (code "113") (name "Net-(B$12-PadOUT)") (class "Default")
      (node (ref "B$12") (pin "OUT") (pinfunction "OUT_OUT") (pintype "bidirectional"))
      (node (ref "U$1") (pin "RF$08_G3") (pinfunction "RF$08_G3_RF$08_G3") (pintype "bidirectional"))
    )
    (net (code "114") (name "Net-(B$13-PadHF)") (class "Default")
      (node (ref "B$13") (pin "HF") (pinfunction "HF_HF") (pintype "bidirectional"))
      (node (ref "S$10") (pin "1") (pinfunction "1_1") (pintype "passive"))
    )
    (net (code "115") (name "Net-(B$13-PadOUT)") (class "Default")
      (node (ref "B$13") (pin "OUT") (pinfunction "OUT_OUT") (pintype "bidirectional"))
      (node (ref "U$1") (pin "RF$09_G4") (pinfunction "RF$09_G4_RF$09_G4") (pintype "bidirectional"))
    )
    (net (code "116") (name "Net-(B$14-PadHF)") (class "Default")
      (node (ref "B$14") (pin "HF") (pinfunction "HF_HF") (pintype "bidirectional"))
      (node (ref "S$11") (pin "1") (pinfunction "1_1") (pintype "passive"))
    )
    (net (code "117") (name "Net-(B$14-PadOUT)") (class "Default")
      (node (ref "B$14") (pin "OUT") (pinfunction "OUT_OUT") (pintype "bidirectional"))
      (node (ref "U$1") (pin "RF$15_G5") (pinfunction "RF$15_G5_RF$15_G5") (pintype "bidirectional"))
    )
    (net (code "118") (name "Net-(B$15-PadHF)") (class "Default")
      (node (ref "B$15") (pin "HF") (pinfunction "HF_HF") (pintype "bidirectional"))
      (node (ref "S$12") (pin "1") (pinfunction "1_1") (pintype "passive"))
    )
    (net (code "119") (name "Net-(B$15-PadOUT)") (class "Default")
      (node (ref "B$15") (pin "OUT") (pinfunction "OUT_OUT") (pintype "bidirectional"))
      (node (ref "U$1") (pin "RF$16_G6") (pinfunction "RF$16_G6_RF$16_G6") (pintype "bidirectional"))
    )
    (net (code "120") (name "Net-(B$16-PadHF)") (class "Default")
      (node (ref "B$16") (pin "HF") (pinfunction "HF_HF") (pintype "bidirectional"))
      (node (ref "S$13") (pin "1") (pinfunction "1_1") (pintype "passive"))
    )
    (net (code "121") (name "Net-(B$16-PadOUT)") (class "Default")
      (node (ref "B$16") (pin "OUT") (pinfunction "OUT_OUT") (pintype "bidirectional"))
      (node (ref "U$1") (pin "RF$20_G7") (pinfunction "RF$20_G7_RF$20_G7") (pintype "bidirectional"))
    )
    (net (code "122") (name "Net-(B$17-PadHF)") (class "Default")
      (node (ref "B$17") (pin "HF") (pinfunction "HF_HF") (pintype "bidirectional"))
      (node (ref "S$14") (pin "1") (pinfunction "1_1") (pintype "passive"))
    )
    (net (code "123") (name "Net-(B$17-PadOUT)") (class "Default")
      (node (ref "B$17") (pin "OUT") (pinfunction "OUT_OUT") (pintype "bidirectional"))
      (node (ref "U$1") (pin "RF$21_G8") (pinfunction "RF$21_G8_RF$21_G8") (pintype "bidirectional"))
    )
    (net (code "124") (name "Net-(B$18-PadHF)") (class "Default")
      (node (ref "B$18") (pin "HF") (pinfunction "HF_HF") (pintype "bidirectional"))
      (node (ref "S$3") (pin "1") (pinfunction "1_1") (pintype "passive"))
    )
    (net (code "125") (name "Net-(B$18-PadOUT)") (class "Default")
      (node (ref "B$18") (pin "OUT") (pinfunction "OUT_OUT") (pintype "bidirectional"))
      (node (ref "U$1") (pin "RF$28_G10") (pinfunction "RF$28_G10_RF$28_G10") (pintype "bidirectional"))
    )
    (net (code "126") (name "Net-(B$19-PadHF)") (class "Default")
      (node (ref "B$19") (pin "HF") (pinfunction "HF_HF") (pintype "bidirectional"))
      (node (ref "S$4") (pin "1") (pinfunction "1_1") (pintype "passive"))
    )
    (net (code "127") (name "Net-(B$19-PadOUT)") (class "Default")
      (node (ref "B$19") (pin "OUT") (pinfunction "OUT_OUT") (pintype "bidirectional"))
      (node (ref "U$1") (pin "RF$32_G11") (pinfunction "RF$32_G11_RF$32_G11") (pintype "bidirectional"))
    )
    (net (code "128") (name "Net-(B$20-PadHF)") (class "Default")
      (node (ref "B$20") (pin "HF") (pinfunction "HF_HF") (pintype "bidirectional"))
      (node (ref "S$6") (pin "1") (pinfunction "1_1") (pintype "passive"))
    )
    (net (code "129") (name "Net-(B$20-PadOUT)") (class "Default")
      (node (ref "B$20") (pin "OUT") (pinfunction "OUT_OUT") (pintype "bidirectional"))
      (node (ref "U$1") (pin "RF$33_G12") (pinfunction "RF$33_G12_RF$33_G12") (pintype "bidirectional"))
    )
    (net (code "130") (name "Net-(B$21-PadHF)") (class "Default")
      (node (ref "B$21") (pin "HF") (pinfunction "HF_HF") (pintype "bidirectional"))
      (node (ref "S$7") (pin "1") (pinfunction "1_1") (pintype "passive"))
    )
    (net (code "131") (name "Net-(B$21-PadOUT)") (class "Default")
      (node (ref "B$21") (pin "OUT") (pinfunction "OUT_OUT") (pintype "bidirectional"))
      (node (ref "U$1") (pin "RF$39_G13") (pinfunction "RF$39_G13_RF$39_G13") (pintype "bidirectional"))
    )
    (net (code "132") (name "Net-(B$22-PadHF)") (class "Default")
      (node (ref "B$22") (pin "HF") (pinfunction "HF_HF") (pintype "bidirectional"))
      (node (ref "S$15") (pin "1") (pinfunction "1_1") (pintype "passive"))
    )
    (net (code "133") (name "Net-(B$22-PadOUT)") (class "Default")
      (node (ref "B$22") (pin "OUT") (pinfunction "OUT_OUT") (pintype "bidirectional"))
      (node (ref "U$1") (pin "RF$40_G14") (pinfunction "RF$40_G14_RF$40_G14") (pintype "bidirectional"))
    )
    (net (code "134") (name "Net-(B$23-PadHF)") (class "Default")
      (node (ref "B$23") (pin "HF") (pinfunction "HF_HF") (pintype "bidirectional"))
      (node (ref "S$16") (pin "1") (pinfunction "1_1") (pintype "passive"))
    )
    (net (code "135") (name "Net-(B$23-PadOUT)") (class "Default")
      (node (ref "B$23") (pin "OUT") (pinfunction "OUT_OUT") (pintype "bidirectional"))
      (node (ref "U$1") (pin "RF$44_G15") (pinfunction "RF$44_G15_RF$44_G15") (pintype "bidirectional"))
    )
    (net (code "136") (name "Net-(B$24-PadHF)") (class "Default")
      (node (ref "B$24") (pin "HF") (pinfunction "HF_HF") (pintype "bidirectional"))
      (node (ref "S$17") (pin "1") (pinfunction "1_1") (pintype "passive"))
    )
    (net (code "137") (name "Net-(B$24-PadOUT)") (class "Default")
      (node (ref "B$24") (pin "OUT") (pinfunction "OUT_OUT") (pintype "bidirectional"))
      (node (ref "U$1") (pin "RF$45_G16") (pinfunction "RF$45_G16_RF$45_G16") (pintype "bidirectional"))
    )
    (net (code "138") (name "Net-(U$2-IN)") (class "Default")
      (node (ref "U$2") (pin "P$1") (pinfunction "IN_P$1") (pintype "bidirectional"))
      (node (ref "U$3") (pin "P$2") (pinfunction "OUT1_P$2") (pintype "bidirectional"))
    )
    (net (code "139") (name "Net-(U$2-OUT1)") (class "Default")
      (node (ref "B$1") (pin "HF") (pinfunction "HF_HF") (pintype "bidirectional"))
      (node (ref "U$2") (pin "P$2") (pinfunction "OUT1_P$2") (pintype "bidirectional"))
    )
    (net (code "140") (name "Net-(U$2-OUT2)") (class "Default")
      (node (ref "B$7") (pin "HF") (pinfunction "HF_HF") (pintype "bidirectional"))
      (node (ref "U$2") (pin "P$3") (pinfunction "OUT2_P$3") (pintype "bidirectional"))
    )
    (net (code "141") (name "Net-(U$3-IN)") (class "Default")
      (node (ref "U$3") (pin "P$1") (pinfunction "IN_P$1") (pintype "bidirectional"))
      (node (ref "U$4") (pin "P$2") (pinfunction "OUT1_P$2") (pintype "bidirectional"))
    )
    (net (code "142") (name "Net-(U$3-OUT2)") (class "Default")
      (node (ref "U$3") (pin "P$3") (pinfunction "OUT2_P$3") (pintype "bidirectional"))
      (node (ref "U$9") (pin "P$1") (pinfunction "IN_P$1") (pintype "bidirectional"))
    )
    (net (code "143") (name "Net-(U$4-IN)") (class "Default")
      (node (ref "S$5") (pin "1") (pinfunction "1_1") (pintype "passive"))
      (node (ref "U$4") (pin "P$1") (pinfunction "IN_P$1") (pintype "bidirectional"))
    )
    (net (code "144") (name "Net-(U$4-OUT2)") (class "Default")
      (node (ref "U$4") (pin "P$3") (pinfunction "OUT2_P$3") (pintype "bidirectional"))
      (node (ref "U$5") (pin "P$1") (pinfunction "IN_P$1") (pintype "bidirectional"))
    )
    (net (code "145") (name "Net-(U$5-OUT1)") (class "Default")
      (node (ref "U$5") (pin "P$2") (pinfunction "OUT1_P$2") (pintype "bidirectional"))
      (node (ref "U$8") (pin "P$1") (pinfunction "IN_P$1") (pintype "bidirectional"))
    )
    (net (code "146") (name "Net-(U$5-OUT2)") (class "Default")
      (node (ref "U$5") (pin "P$3") (pinfunction "OUT2_P$3") (pintype "bidirectional"))
      (node (ref "U$6") (pin "P$1") (pinfunction "IN_P$1") (pintype "bidirectional"))
    )
    (net (code "147") (name "Net-(U$6-OUT1)") (class "Default")
      (node (ref "B$3") (pin "HF") (pinfunction "HF_HF") (pintype "bidirectional"))
      (node (ref "U$6") (pin "P$2") (pinfunction "OUT1_P$2") (pintype "bidirectional"))
    )
    (net (code "148") (name "Net-(U$6-OUT2)") (class "Default")
      (node (ref "B$2") (pin "HF") (pinfunction "HF_HF") (pintype "bidirectional"))
      (node (ref "U$6") (pin "P$3") (pinfunction "OUT2_P$3") (pintype "bidirectional"))
    )
    (net (code "149") (name "Net-(U$8-OUT1)") (class "Default")
      (node (ref "B$5") (pin "HF") (pinfunction "HF_HF") (pintype "bidirectional"))
      (node (ref "U$8") (pin "P$2") (pinfunction "OUT1_P$2") (pintype "bidirectional"))
    )
    (net (code "150") (name "Net-(U$8-OUT2)") (class "Default")
      (node (ref "B$4") (pin "HF") (pinfunction "HF_HF") (pintype "bidirectional"))
      (node (ref "U$8") (pin "P$3") (pinfunction "OUT2_P$3") (pintype "bidirectional"))
    )
    (net (code "151") (name "Net-(U$9-OUT1)") (class "Default")
      (node (ref "B$9") (pin "HF") (pinfunction "HF_HF") (pintype "bidirectional"))
      (node (ref "U$9") (pin "P$2") (pinfunction "OUT1_P$2") (pintype "bidirectional"))
    )
    (net (code "152") (name "Net-(U$9-OUT2)") (class "Default")
      (node (ref "B$8") (pin "HF") (pinfunction "HF_HF") (pintype "bidirectional"))
      (node (ref "U$9") (pin "P$3") (pinfunction "OUT2_P$3") (pintype "bidirectional"))
    )
    (net (code "153") (name "Net-(U$10-1)") (class "Default")
      (node (ref "B$1") (pin "OUT") (pinfunction "OUT_OUT") (pintype "bidirectional"))
      (node (ref "U$10") (pin "IN") (pinfunction "1_IN") (pintype "passive"))
      (node (ref "U$13") (pin "OUT") (pinfunction "2_OUT") (pintype "passive"))
    )
    (net (code "154") (name "Net-(U$13-1)") (class "Default")
      (node (ref "L$2") (pin "IN") (pinfunction "IN_IN") (pintype "passive"))
      (node (ref "U$13") (pin "IN") (pinfunction "1_IN") (pintype "passive"))
    )
    (net (code "155") (name "Net-(U$16-1)") (class "Default")
      (node (ref "B$2") (pin "OUT") (pinfunction "OUT_OUT") (pintype "bidirectional"))
      (node (ref "U$16") (pin "IN") (pinfunction "1_IN") (pintype "passive"))
      (node (ref "U$20") (pin "OUT") (pinfunction "2_OUT") (pintype "passive"))
    )
    (net (code "156") (name "Net-(U$17-1)") (class "Default")
      (node (ref "L$1") (pin "IN") (pinfunction "IN_IN") (pintype "passive"))
      (node (ref "U$17") (pin "IN") (pinfunction "1_IN") (pintype "passive"))
    )
    (net (code "157") (name "Net-(U$17-2)") (class "Default")
      (node (ref "B$7") (pin "OUT") (pinfunction "OUT_OUT") (pintype "bidirectional"))
      (node (ref "U$17") (pin "OUT") (pinfunction "2_OUT") (pintype "passive"))
      (node (ref "U$7") (pin "IN") (pinfunction "1_IN") (pintype "passive"))
    )
    (net (code "158") (name "Net-(U$20-1)") (class "Default")
      (node (ref "L$3") (pin "IN") (pinfunction "IN_IN") (pintype "passive"))
      (node (ref "U$20") (pin "IN") (pinfunction "1_IN") (pintype "passive"))
    )
    (net (code "159") (name "Net-(U$21-1)") (class "Default")
      (node (ref "B$4") (pin "OUT") (pinfunction "OUT_OUT") (pintype "bidirectional"))
      (node (ref "U$21") (pin "IN") (pinfunction "1_IN") (pintype "passive"))
      (node (ref "U$29") (pin "OUT") (pinfunction "2_OUT") (pintype "passive"))
    )
    (net (code "160") (name "Net-(U$22-1)") (class "Default")
      (node (ref "B$3") (pin "OUT") (pinfunction "OUT_OUT") (pintype "bidirectional"))
      (node (ref "U$22") (pin "IN") (pinfunction "1_IN") (pintype "passive"))
      (node (ref "U$26") (pin "OUT") (pinfunction "2_OUT") (pintype "passive"))
    )
    (net (code "161") (name "Net-(U$26-1)") (class "Default")
      (node (ref "L$4") (pin "IN") (pinfunction "IN_IN") (pintype "passive"))
      (node (ref "U$26") (pin "IN") (pinfunction "1_IN") (pintype "passive"))
    )
    (net (code "162") (name "Net-(U$29-1)") (class "Default")
      (node (ref "L$5") (pin "IN") (pinfunction "IN_IN") (pintype "passive"))
      (node (ref "U$29") (pin "IN") (pinfunction "1_IN") (pintype "passive"))
    )
    (net (code "163") (name "Net-(U$30-1)") (class "Default")
      (node (ref "B$5") (pin "OUT") (pinfunction "OUT_OUT") (pintype "bidirectional"))
      (node (ref "U$30") (pin "IN") (pinfunction "1_IN") (pintype "passive"))
      (node (ref "U$33") (pin "OUT") (pinfunction "2_OUT") (pintype "passive"))
    )
    (net (code "164") (name "Net-(U$33-1)") (class "Default")
      (node (ref "L$6") (pin "IN") (pinfunction "IN_IN") (pintype "passive"))
      (node (ref "U$33") (pin "IN") (pinfunction "1_IN") (pintype "passive"))
    )
    (net (code "165") (name "Net-(U$34-1)") (class "Default")
      (node (ref "B$8") (pin "OUT") (pinfunction "OUT_OUT") (pintype "bidirectional"))
      (node (ref "U$34") (pin "IN") (pinfunction "1_IN") (pintype "passive"))
      (node (ref "U$37") (pin "OUT") (pinfunction "2_OUT") (pintype "passive"))
    )
    (net (code "166") (name "Net-(U$37-1)") (class "Default")
      (node (ref "L$7") (pin "IN") (pinfunction "IN_IN") (pintype "passive"))
      (node (ref "U$37") (pin "IN") (pinfunction "1_IN") (pintype "passive"))
    )
    (net (code "167") (name "Net-(U$38-1)") (class "Default")
      (node (ref "B$9") (pin "OUT") (pinfunction "OUT_OUT") (pintype "bidirectional"))
      (node (ref "U$38") (pin "IN") (pinfunction "1_IN") (pintype "passive"))
      (node (ref "U$41") (pin "OUT") (pinfunction "2_OUT") (pintype "passive"))
    )
    (net (code "168") (name "Net-(U$41-1)") (class "Default")
      (node (ref "L$8") (pin "IN") (pinfunction "IN_IN") (pintype "passive"))
      (node (ref "U$41") (pin "IN") (pinfunction "1_IN") (pintype "passive"))
    )
    (net (code "169") (name "unconnected-(U$1-PadRF$GND)") (class "Default")
      (node (ref "U$1") (pin "RF$GND") (pinfunction "RF$GND_RF$GND") (pintype "bidirectional"))
    )
    (net (code "170") (name "unconnected-(U$1-PadRF$GND1)") (class "Default")
      (node (ref "U$1") (pin "RF$GND1") (pinfunction "RF$GND1_RF$GND1") (pintype "bidirectional"))
    )
    (net (code "171") (name "unconnected-(U$1-PadRF$GND2)") (class "Default")
      (node (ref "U$1") (pin "RF$GND2") (pinfunction "RF$GND2_RF$GND2") (pintype "bidirectional"))
    )
    (net (code "172") (name "unconnected-(U$1-PadRF$GND3)") (class "Default")
      (node (ref "U$1") (pin "RF$GND3") (pinfunction "RF$GND3_RF$GND3") (pintype "bidirectional"))
    )
    (net (code "173") (name "unconnected-(U$1-PadRF$GND4)") (class "Default")
      (node (ref "U$1") (pin "RF$GND4") (pinfunction "RF$GND4_RF$GND4") (pintype "bidirectional"))
    )
    (net (code "174") (name "unconnected-(U$1-PadRF$GND5)") (class "Default")
      (node (ref "U$1") (pin "RF$GND5") (pinfunction "RF$GND5_RF$GND5") (pintype "bidirectional"))
    )
    (net (code "175") (name "unconnected-(U$1-PadRF$GND6)") (class "Default")
      (node (ref "U$1") (pin "RF$GND6") (pinfunction "RF$GND6_RF$GND6") (pintype "bidirectional"))
    )
    (net (code "176") (name "unconnected-(U$1-PadRF$GND7)") (class "Default")
      (node (ref "U$1") (pin "RF$GND7") (pinfunction "RF$GND7_RF$GND7") (pintype "bidirectional"))
    )
  )
)
